# 1-Schematic_LED_Matrix.net
KiCad netlist of a schematic drawn in EasyEDA
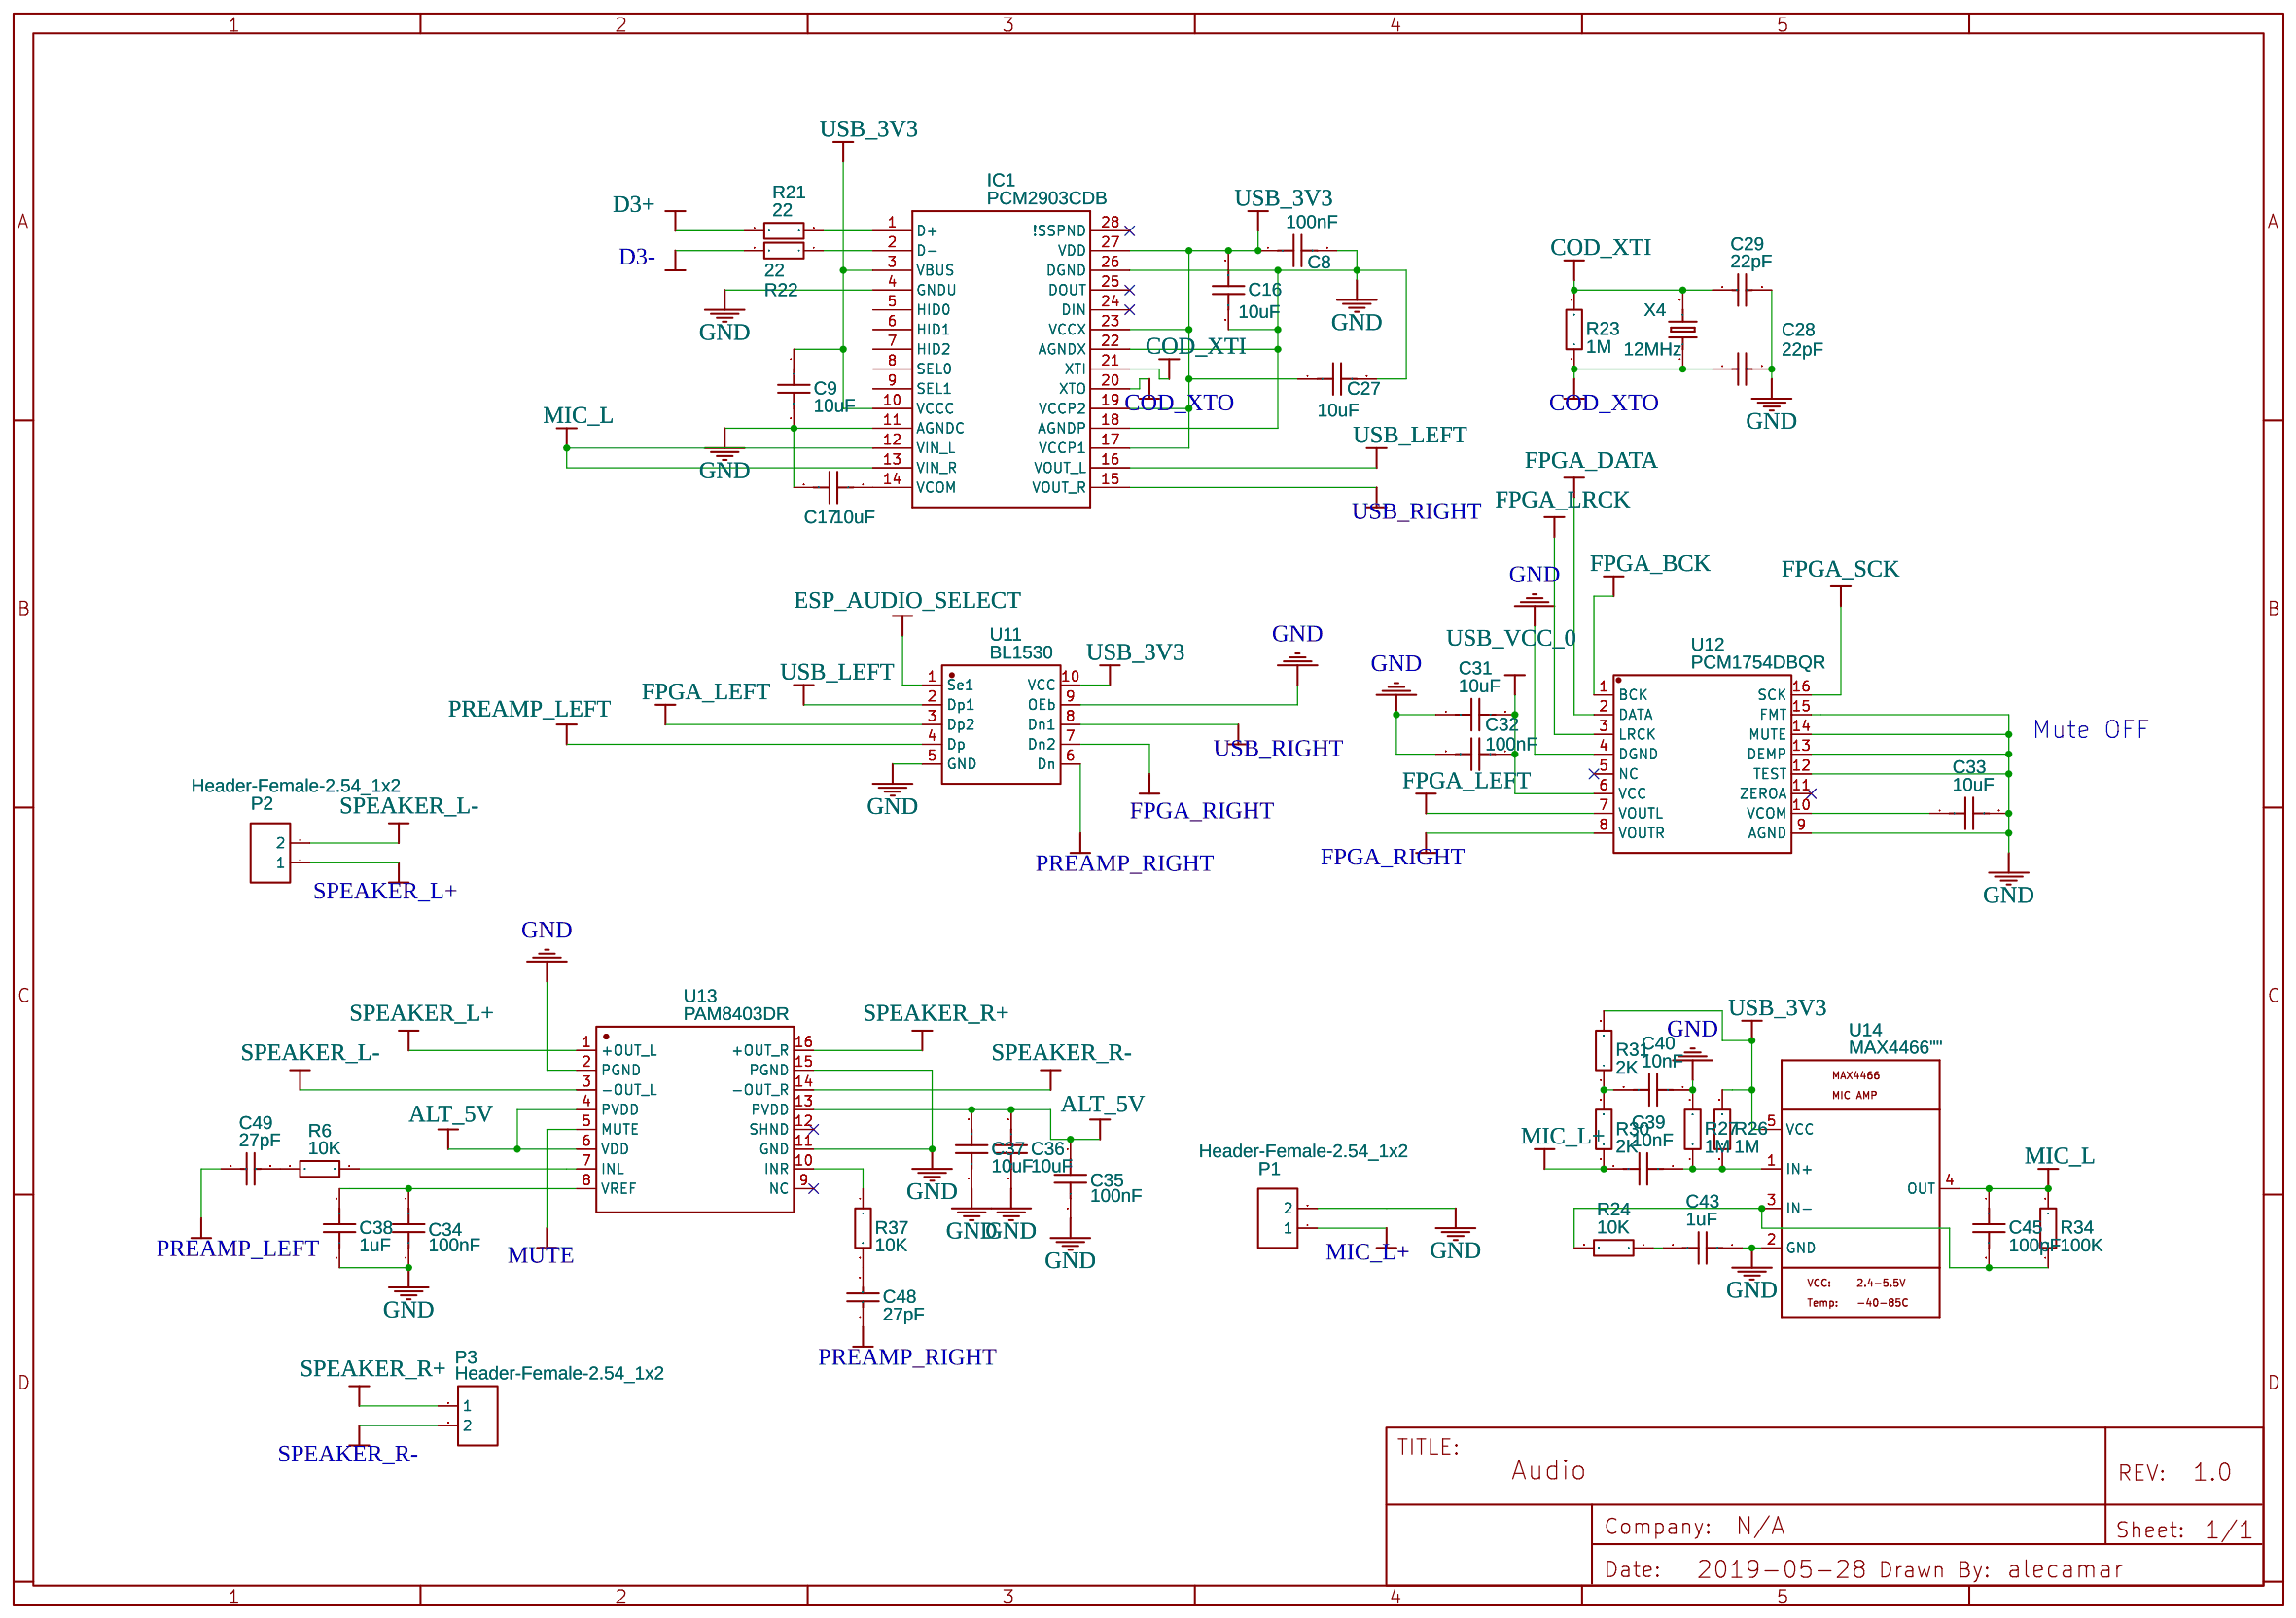
[diagram p0: Audio]
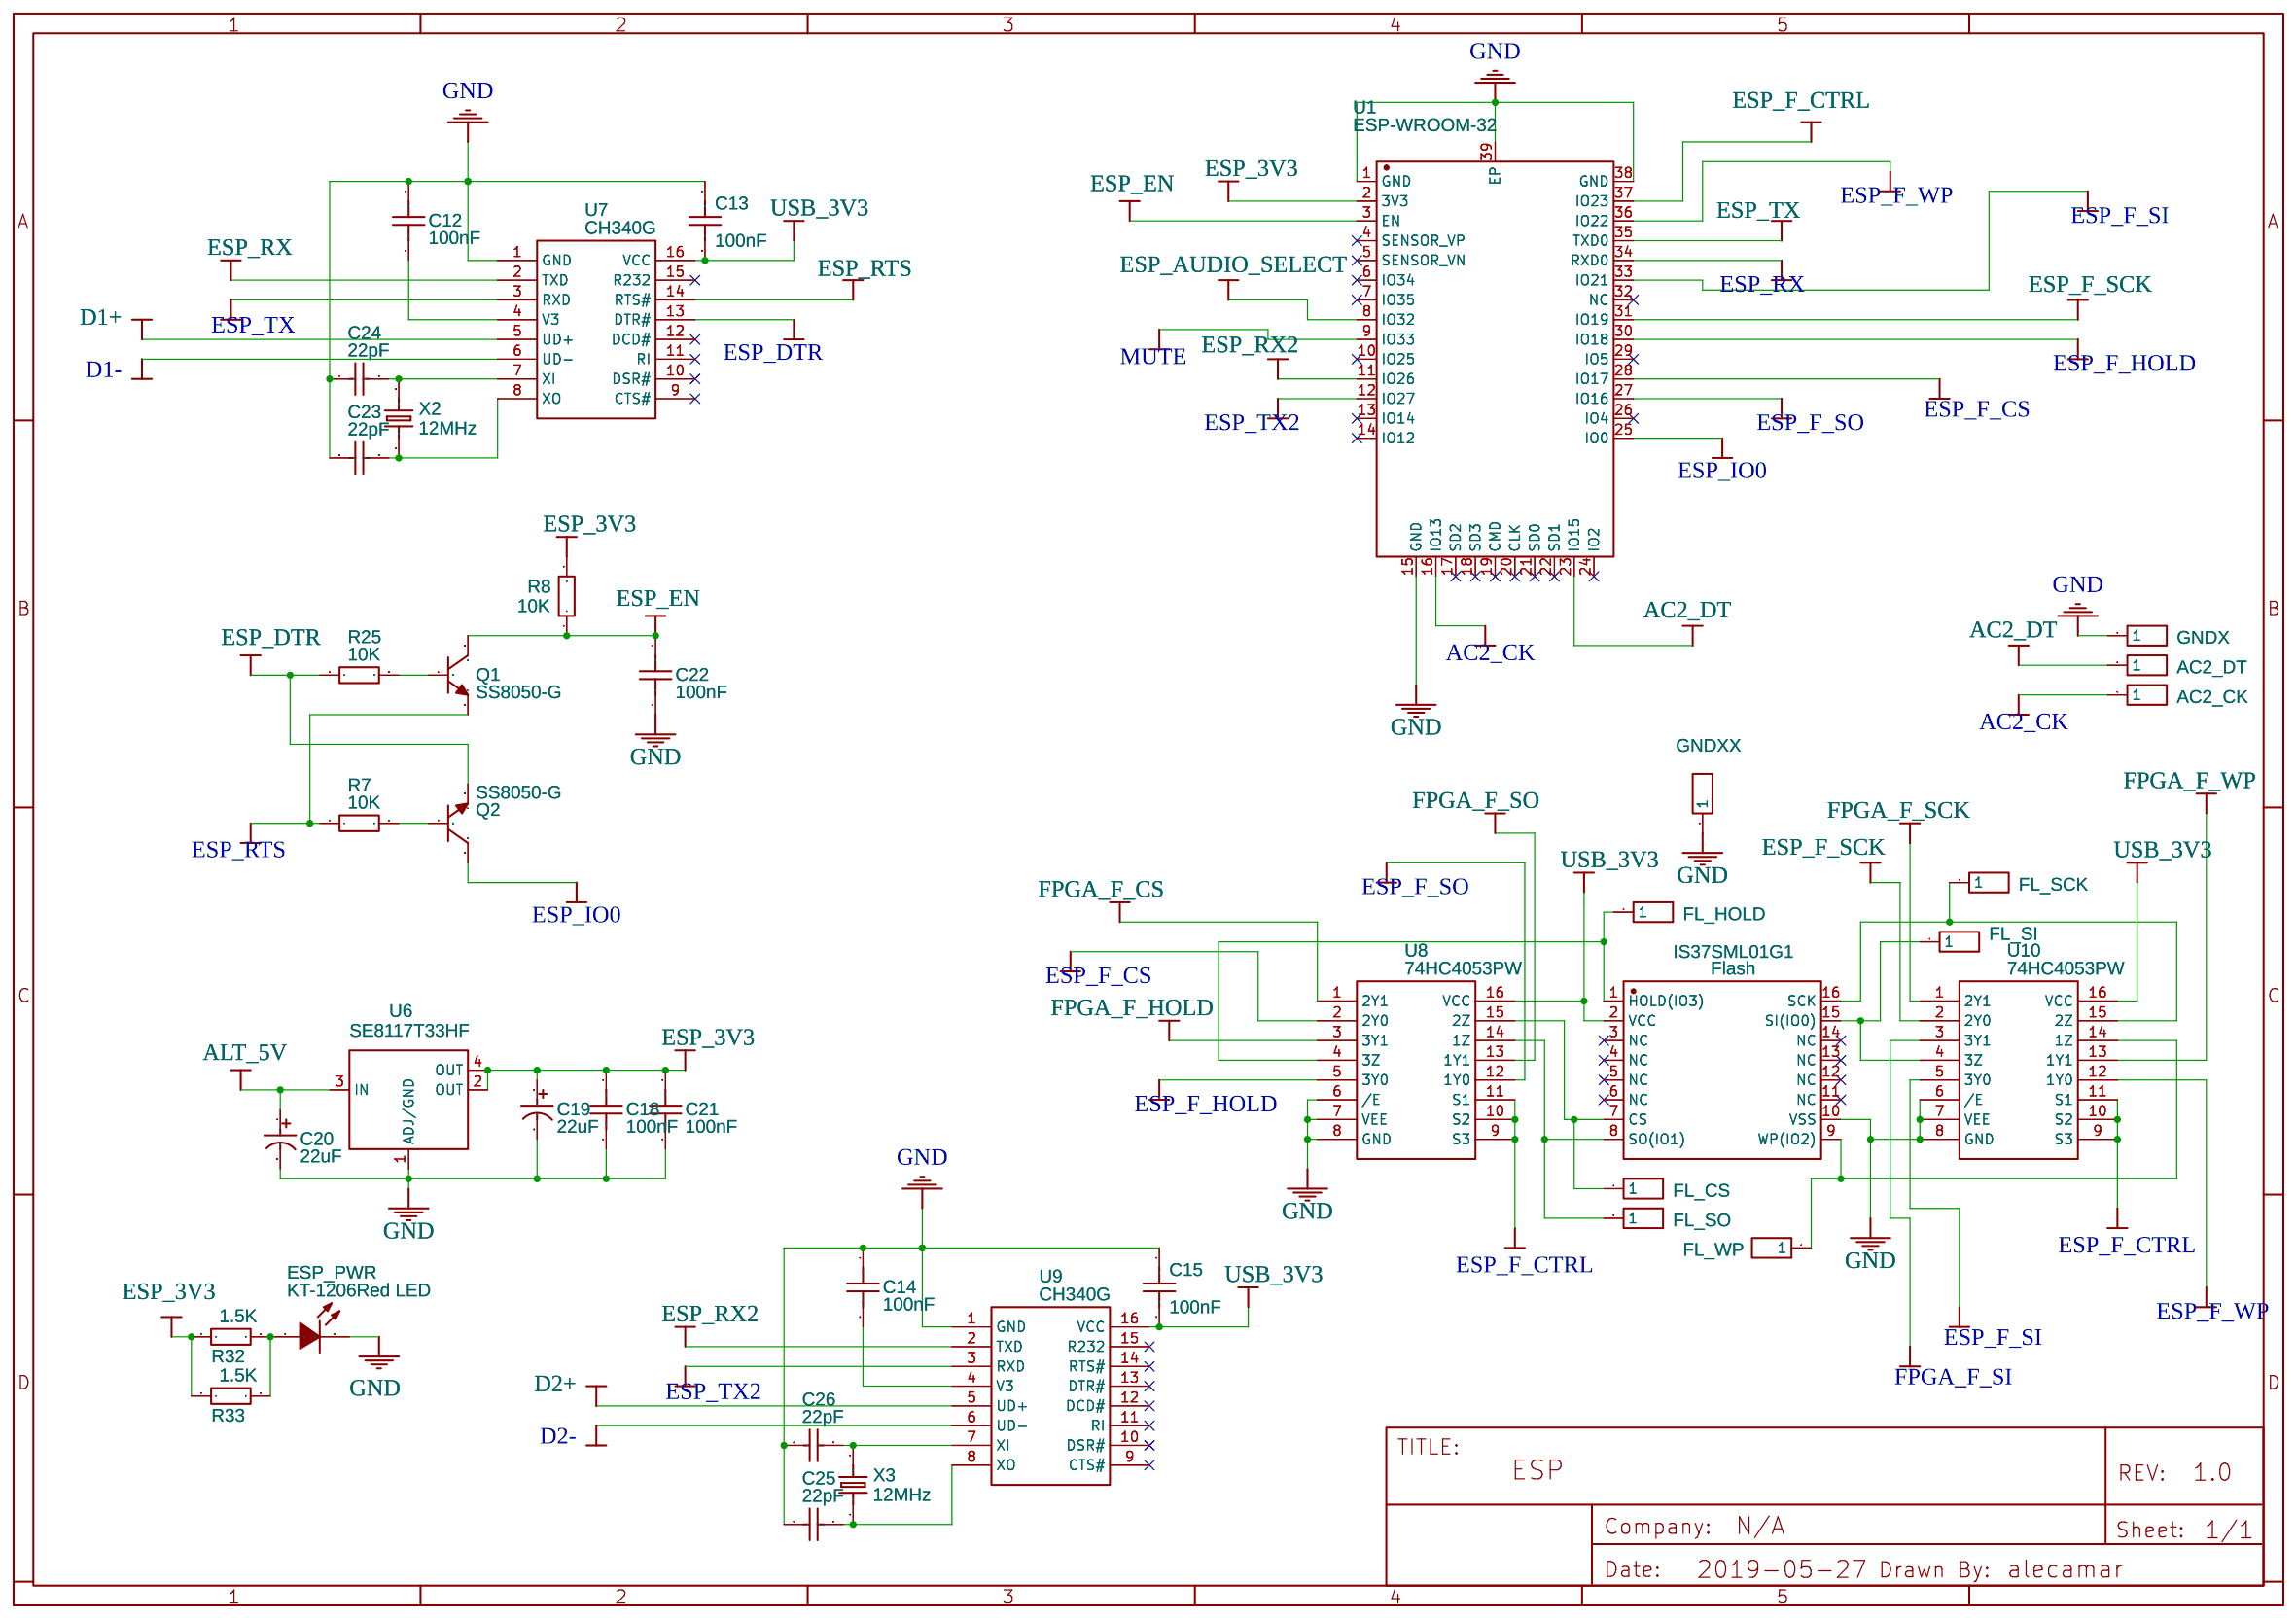
[diagram p1: ESP]
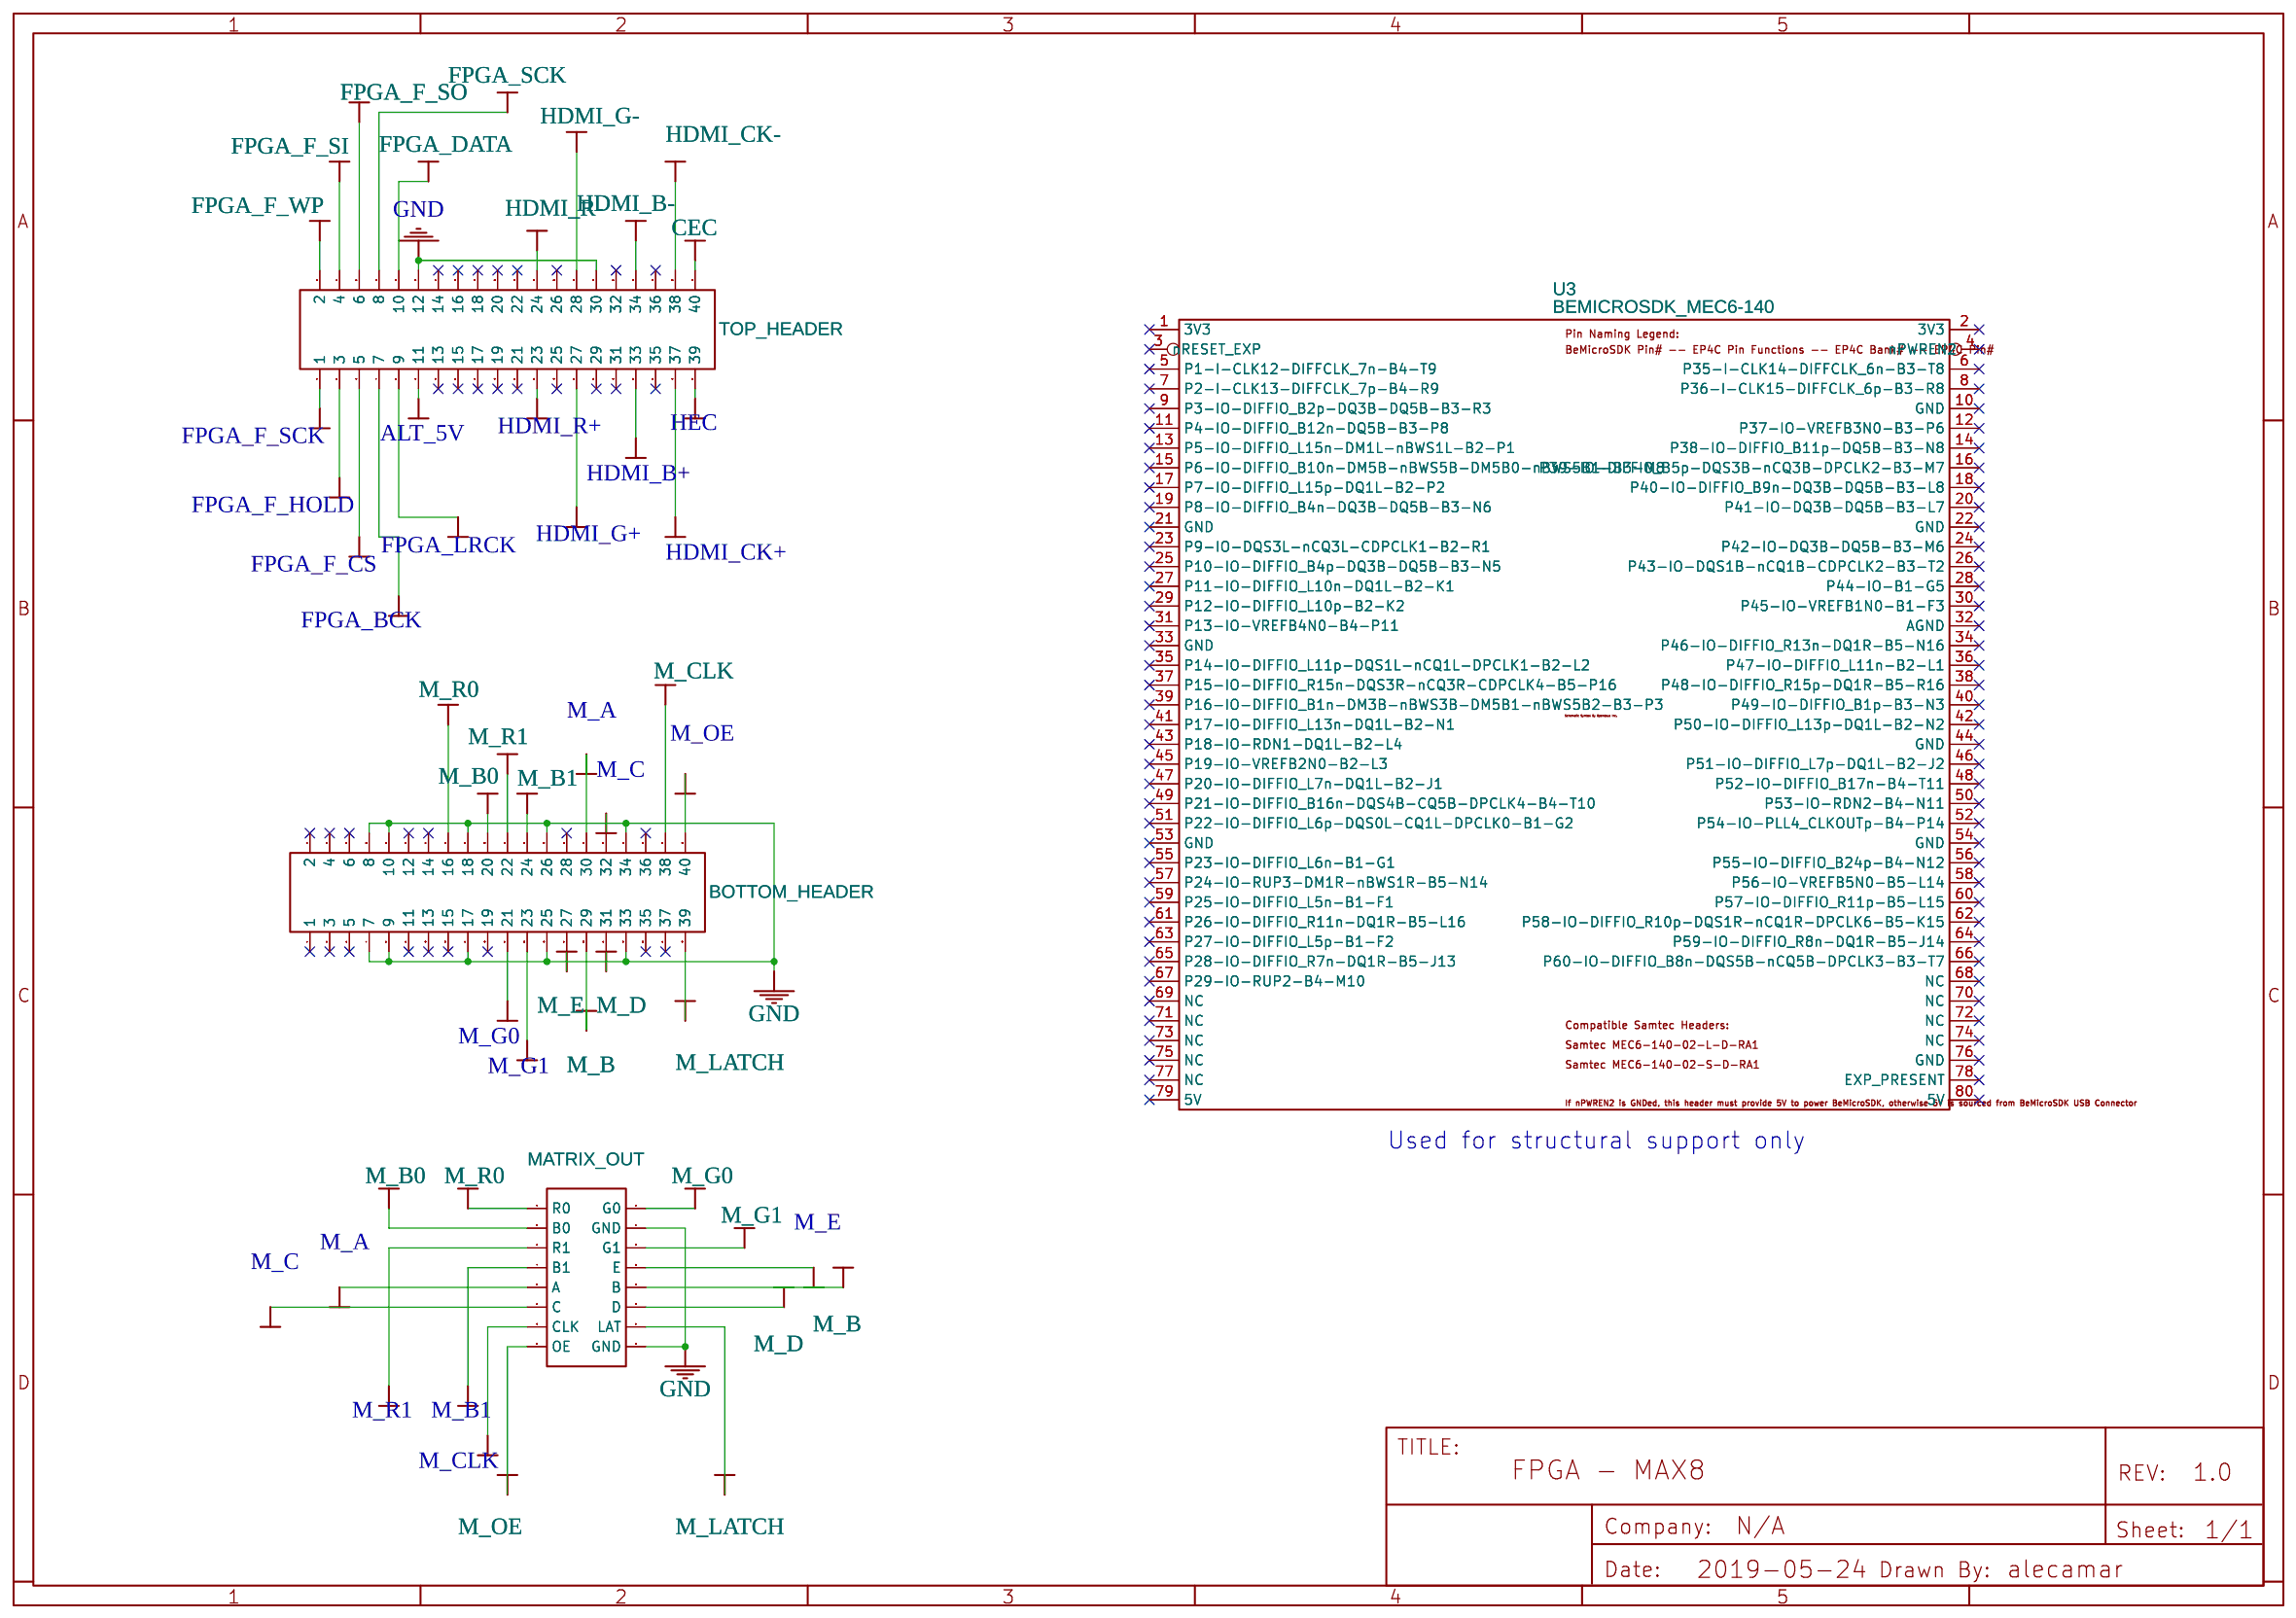
[diagram p2: FPGA]
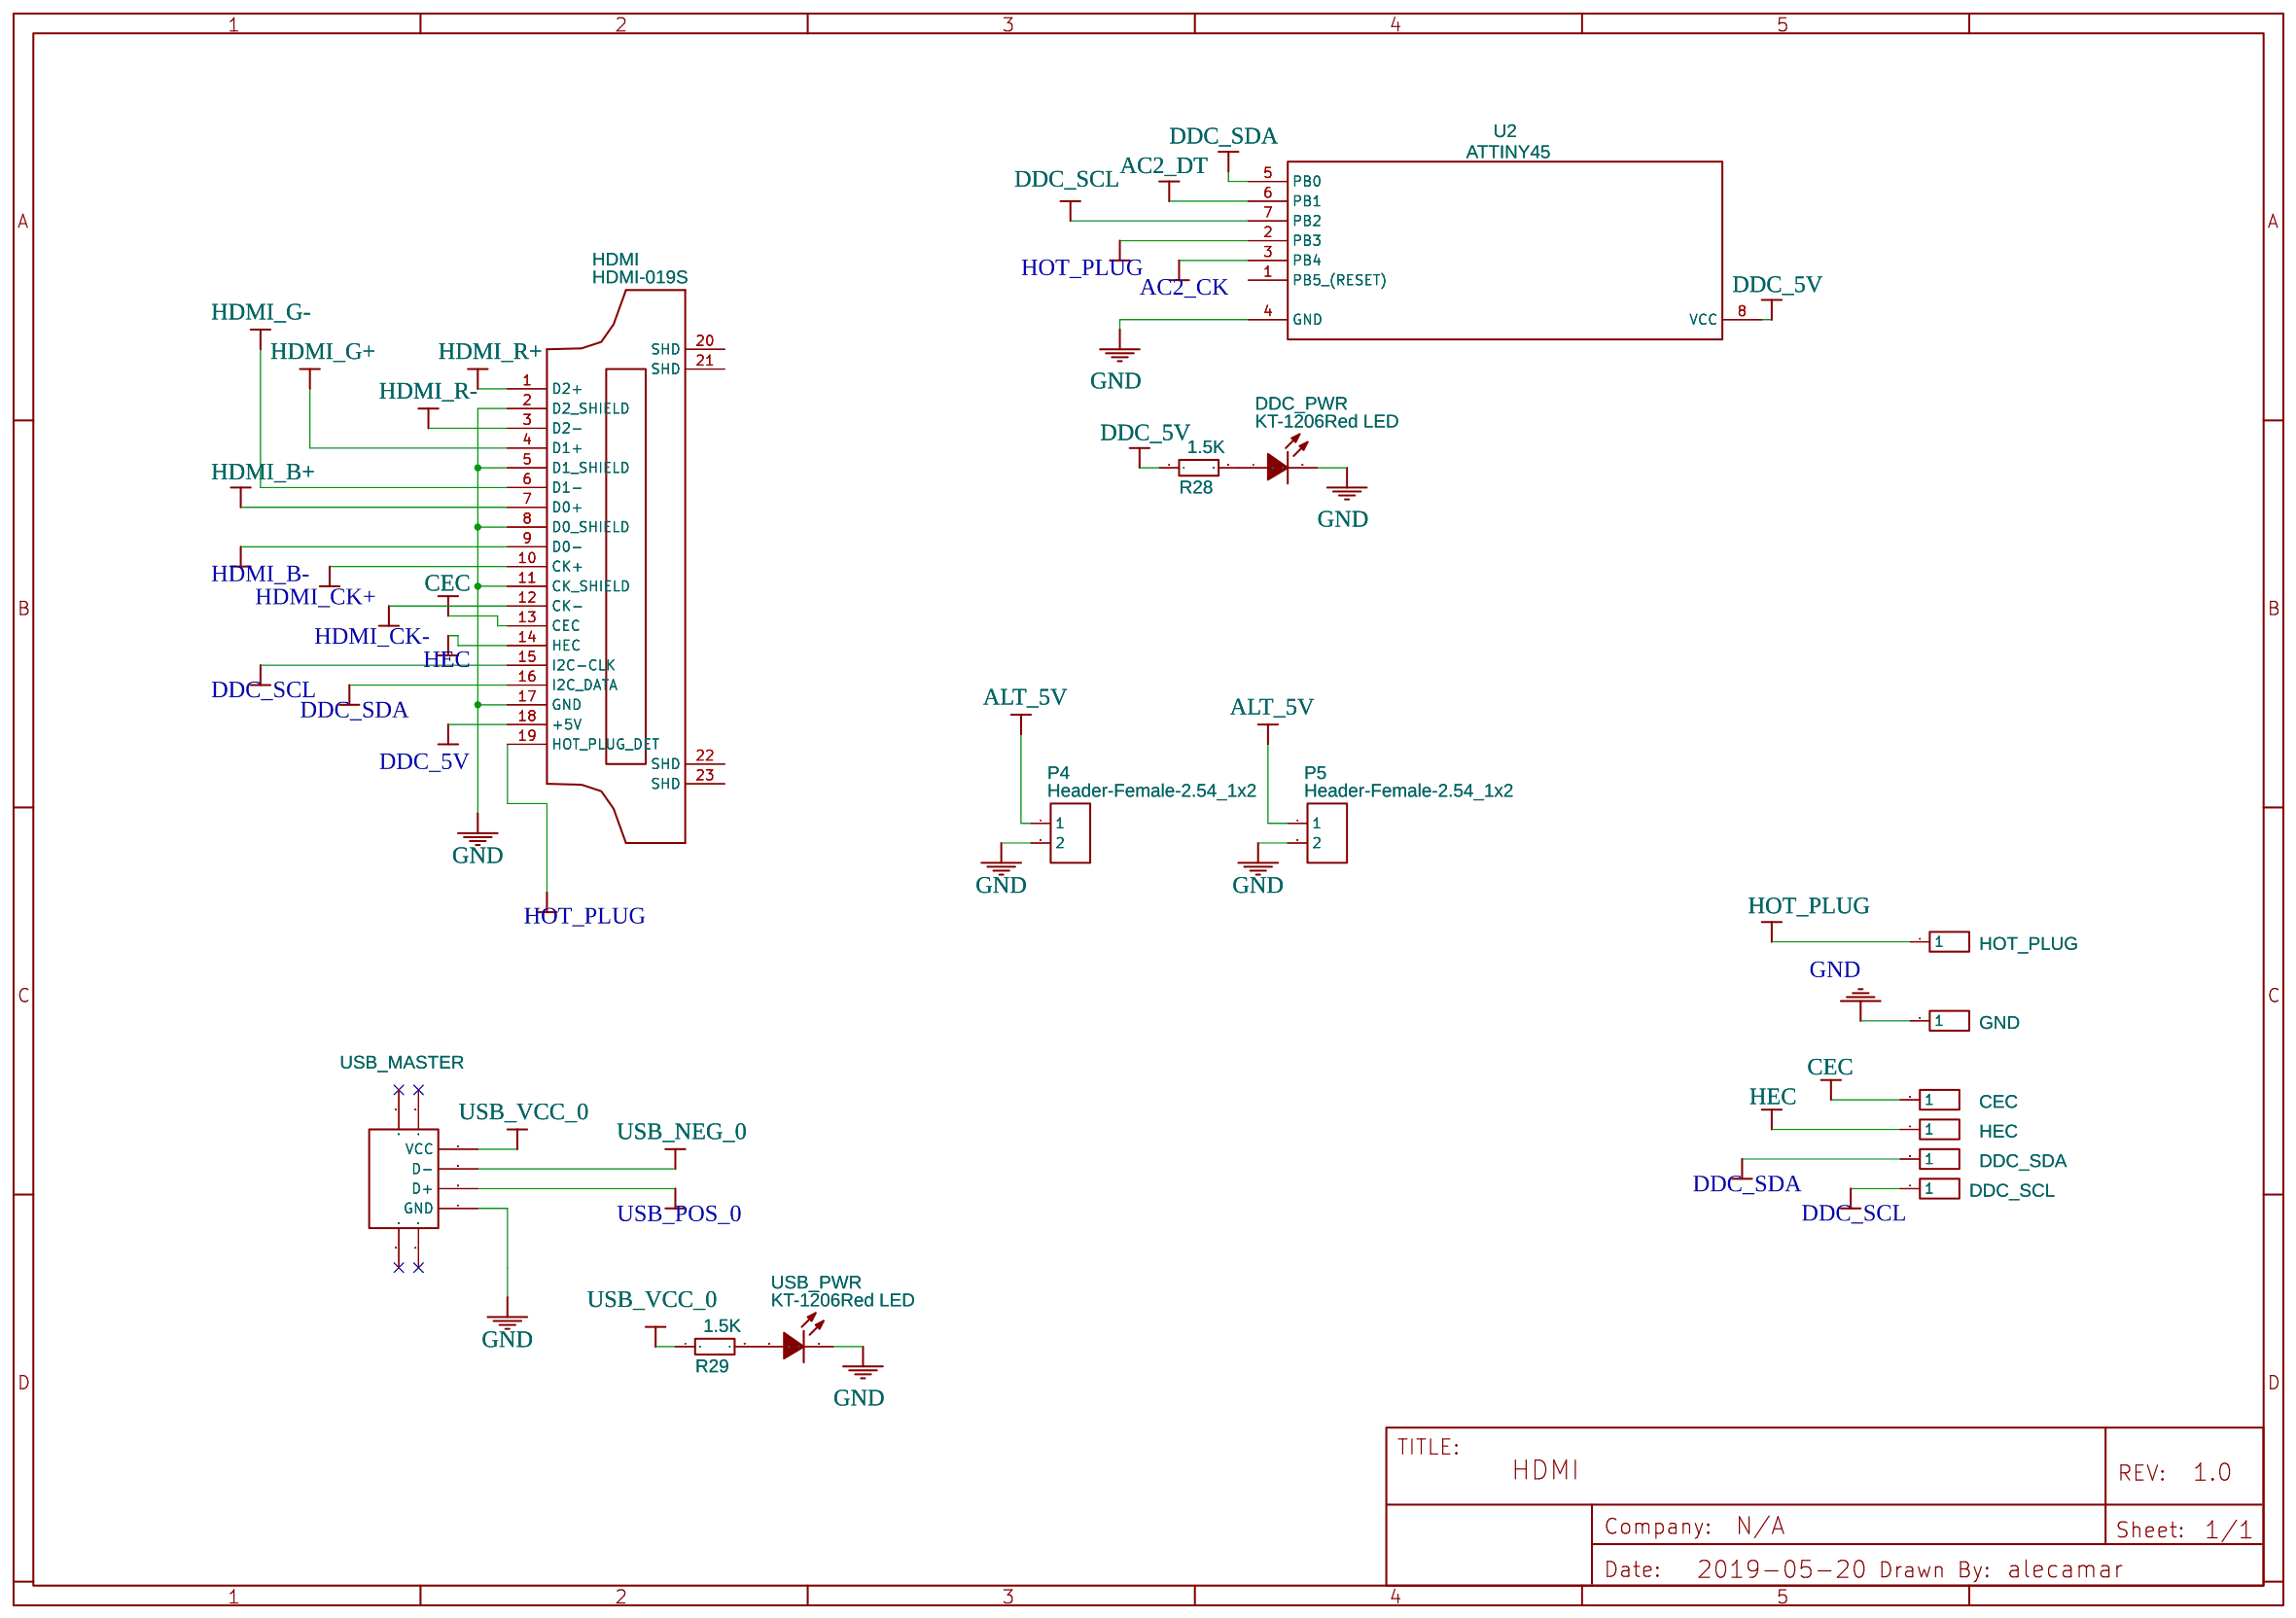
[diagram p3: IO]
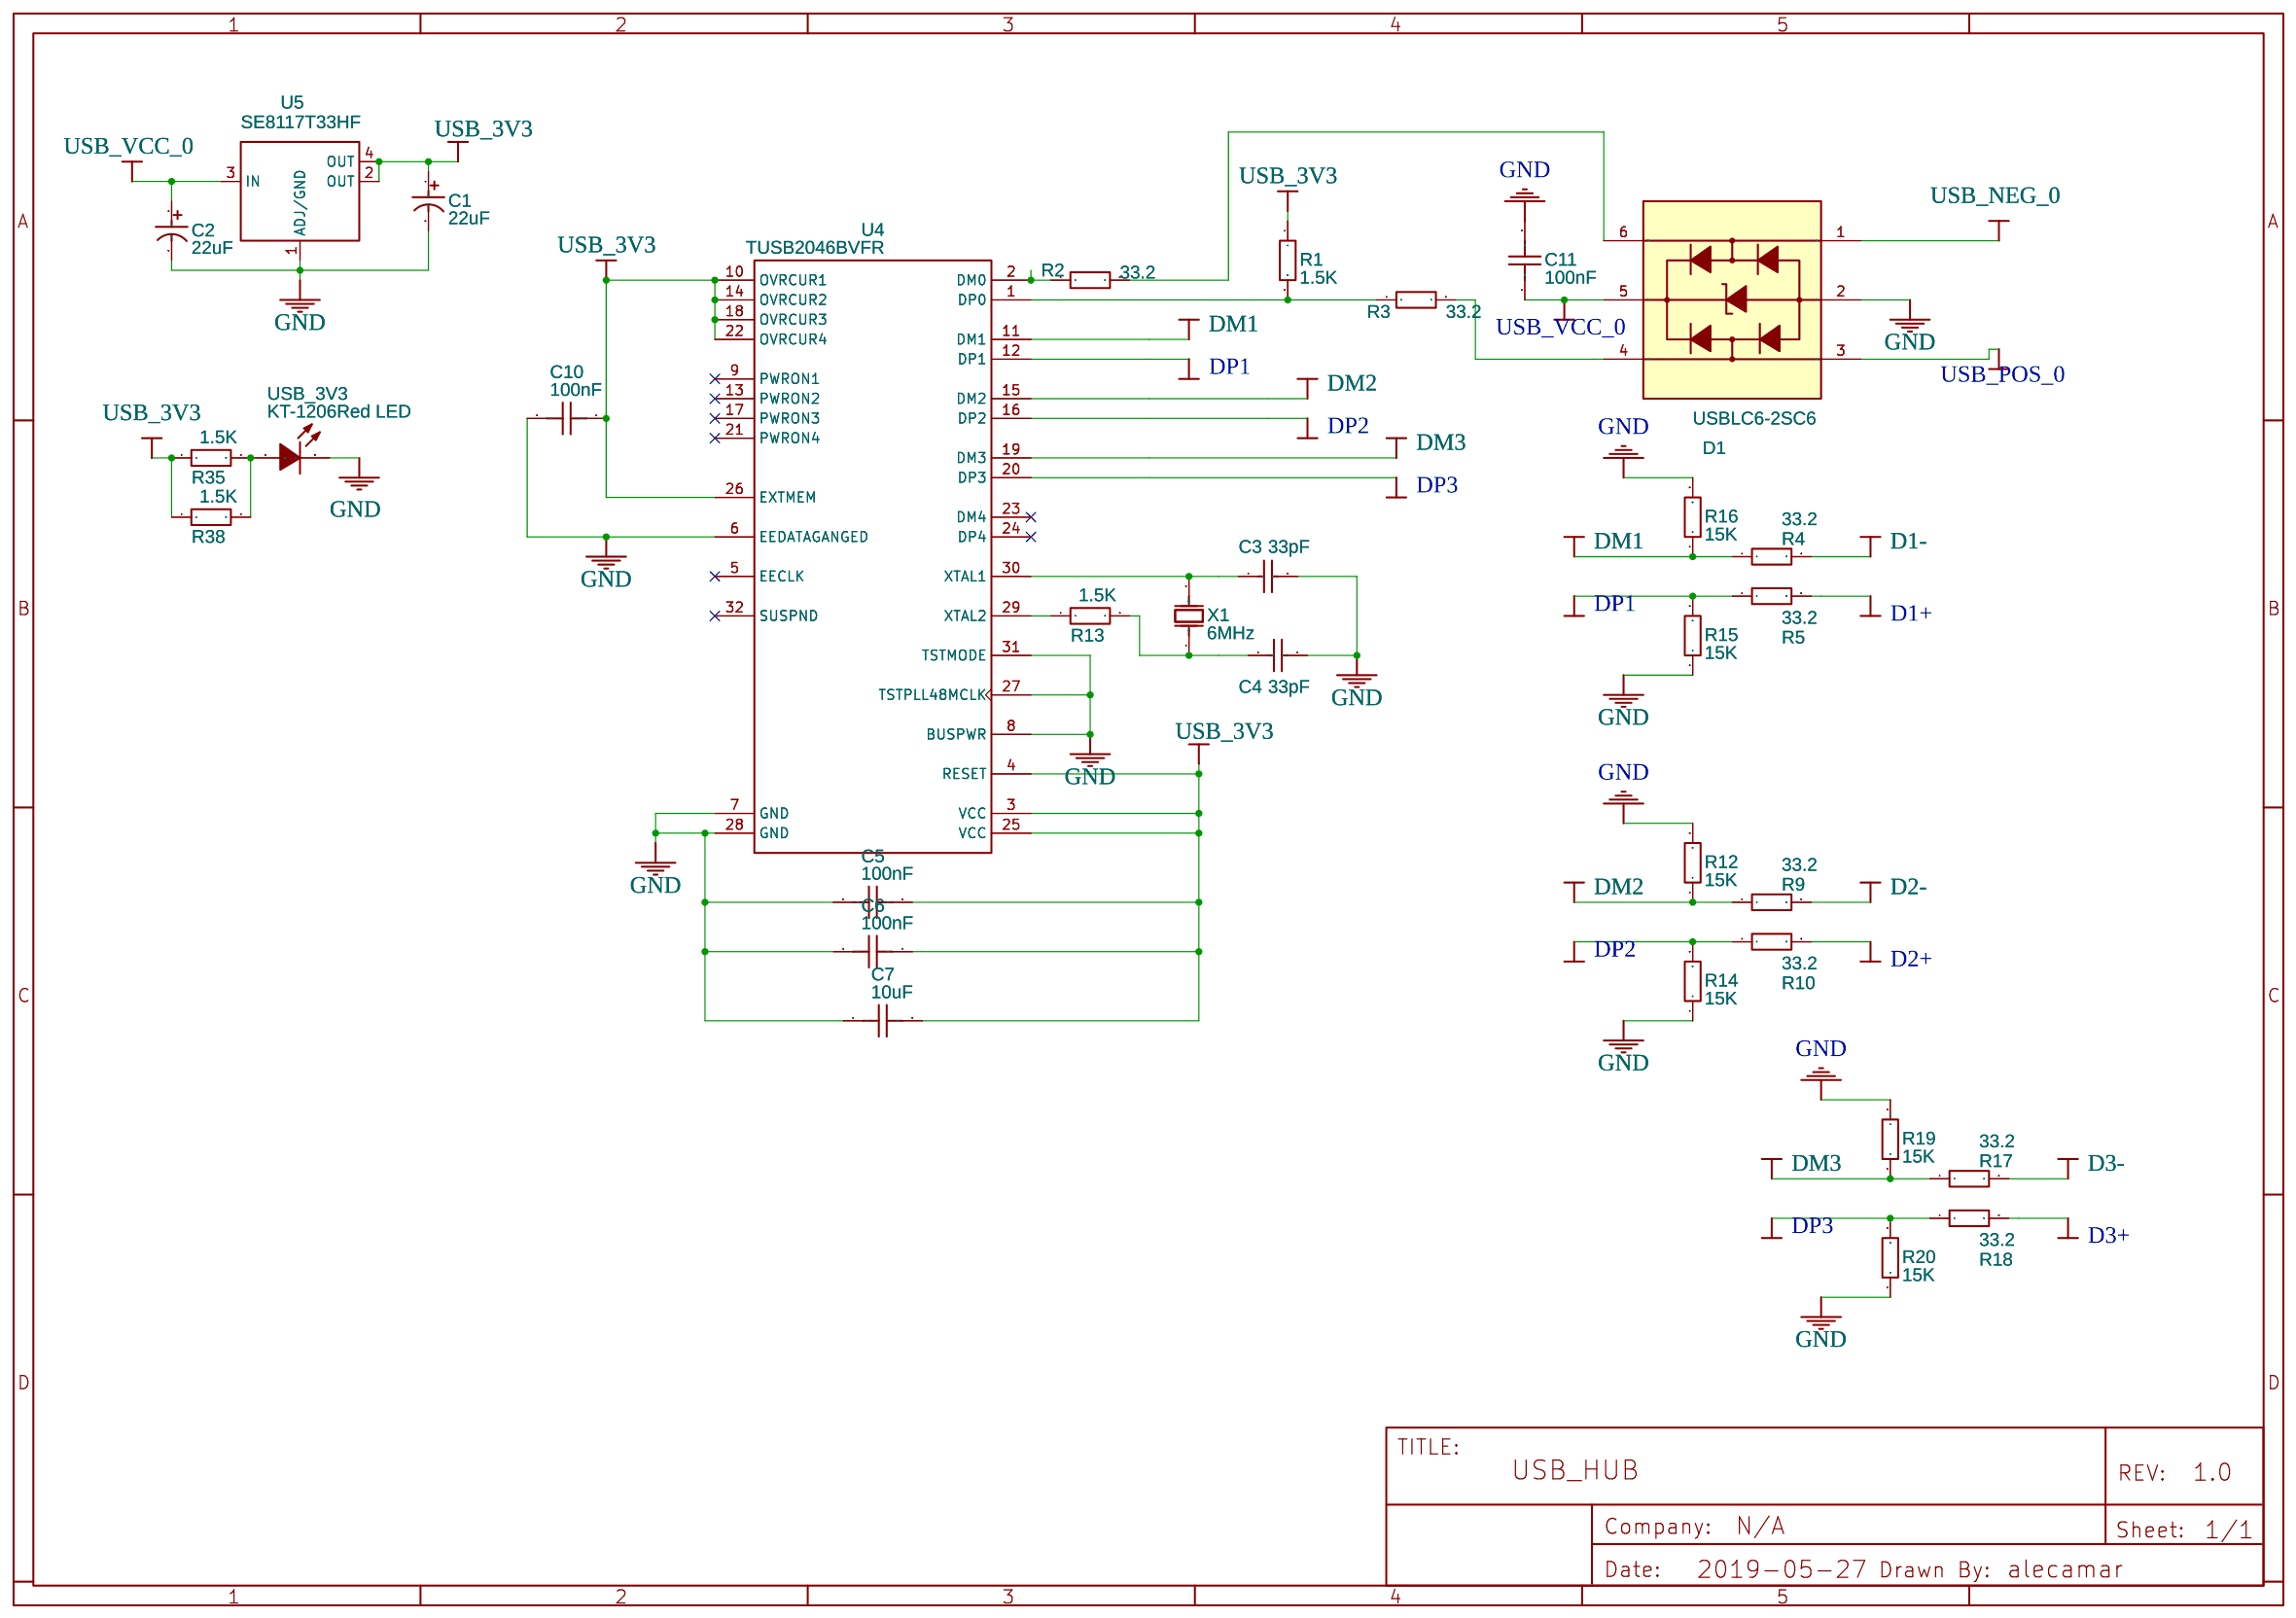
[diagram p4: USB_HUB]

(export (version "E")
  (design (tool "Eeschema 10.0.6"))
  (components
    (comp (ref "C8")
      (value "100nF")
      (fields
        (field (name "BOM_Manufacturer Part") "GRM319R71H104KA01D")
        (field (name "BOM_Supplier Part") "C86047")
      )
      (libsource (lib "") (part "GRM319R71H104KA01D_1"))
    )
    (comp (ref "C9")
      (value "10uF")
      (fields
        (field (name "BOM_Manufacturer Part") "GRM31MB31A106KE18L")
        (field (name "BOM_Supplier Part") "C162498")
      )
      (libsource (lib "") (part "GRM31MB31A106KE18L_2"))
    )
    (comp (ref "C16")
      (value "10uF")
      (fields
        (field (name "BOM_Manufacturer Part") "GRM31MB31A106KE18L")
        (field (name "BOM_Supplier Part") "C162498")
      )
      (libsource (lib "") (part "GRM31MB31A106KE18L_2"))
    )
    (comp (ref "C17")
      (value "10uF")
      (fields
        (field (name "BOM_Manufacturer Part") "GRM31MB31A106KE18L")
        (field (name "BOM_Supplier Part") "C162498")
      )
      (libsource (lib "") (part "GRM31MB31A106KE18L_3"))
    )
    (comp (ref "C27")
      (value "10uF")
      (fields
        (field (name "BOM_Manufacturer Part") "GRM31MB31A106KE18L")
        (field (name "BOM_Supplier Part") "C162498")
      )
      (libsource (lib "") (part "GRM31MB31A106KE18L"))
    )
    (comp (ref "C28")
      (value "22pF")
      (fields
        (field (name "BOM_Manufacturer Part") "1206CG220J500NT")
        (field (name "BOM_Supplier Part") "C1896")
      )
      (libsource (lib "") (part "1206CG220J500NT"))
    )
    (comp (ref "C29")
      (value "22pF")
      (fields
        (field (name "BOM_Manufacturer Part") "1206CG220J500NT")
        (field (name "BOM_Supplier Part") "C1896")
      )
      (libsource (lib "") (part "1206CG220J500NT"))
    )
    (comp (ref "C31")
      (value "10uF")
      (fields
        (field (name "BOM_Manufacturer Part") "GRM31MB31A106KE18L")
        (field (name "BOM_Supplier Part") "C162498")
      )
      (libsource (lib "") (part "GRM31MB31A106KE18L"))
    )
    (comp (ref "C32")
      (value "100nF")
      (fields
        (field (name "BOM_Manufacturer Part") "GRM319R71H104KA01D")
        (field (name "BOM_Supplier Part") "C86047")
      )
      (libsource (lib "") (part "GRM319R71H104KA01D_2"))
    )
    (comp (ref "C33")
      (value "10uF")
      (fields
        (field (name "BOM_Manufacturer Part") "GRM31MB31A106KE18L")
        (field (name "BOM_Supplier Part") "C162498")
      )
      (libsource (lib "") (part "GRM31MB31A106KE18L"))
    )
    (comp (ref "C34")
      (value "100nF")
      (fields
        (field (name "BOM_Manufacturer Part") "GRM319R71H104KA01D")
        (field (name "BOM_Supplier Part") "C86047")
      )
      (libsource (lib "") (part "GRM319R71H104KA01D"))
    )
    (comp (ref "C35")
      (value "100nF")
      (fields
        (field (name "BOM_Manufacturer Part") "GRM319R71H104KA01D")
        (field (name "BOM_Supplier Part") "C86047")
      )
      (libsource (lib "") (part "GRM319R71H104KA01D"))
    )
    (comp (ref "C36")
      (value "10uF")
      (fields
        (field (name "BOM_Manufacturer Part") "GRM31MB31A106KE18L")
        (field (name "BOM_Supplier Part") "C162498")
      )
      (libsource (lib "") (part "GRM31MB31A106KE18L_1"))
    )
    (comp (ref "C37")
      (value "10uF")
      (fields
        (field (name "BOM_Manufacturer Part") "GRM31MB31A106KE18L")
        (field (name "BOM_Supplier Part") "C162498")
      )
      (libsource (lib "") (part "GRM31MB31A106KE18L_1"))
    )
    (comp (ref "C38")
      (value "1uF")
      (fields
        (field (name "BOM_Manufacturer Part") "C1206C105M4RAC7800")
        (field (name "BOM_Supplier Part") "C141188")
      )
      (libsource (lib "") (part "C1206C105M4RAC7800_1"))
    )
    (comp (ref "C39")
      (value "10nF")
      (fields
        (field (name "BOM_Manufacturer Part") "TCC1206X7R103K102FT")
        (field (name "BOM_Supplier Part") "C344191")
      )
      (libsource (lib "") (part "TCC1206X7R103K102FT"))
    )
    (comp (ref "C40")
      (value "10nF")
      (fields
        (field (name "BOM_Manufacturer Part") "TCC1206X7R103K102FT")
        (field (name "BOM_Supplier Part") "C344191")
      )
      (libsource (lib "") (part "TCC1206X7R103K102FT"))
    )
    (comp (ref "C43")
      (value "1uF")
      (fields
        (field (name "BOM_Manufacturer Part") "C1206C105M4RAC7800")
        (field (name "BOM_Supplier Part") "C141188")
      )
      (libsource (lib "") (part "C1206C105M4RAC7800"))
    )
    (comp (ref "C45")
      (value "100pF")
      (fields
        (field (name "BOM_Manufacturer Part") "CL31C101JGFNNNE")
        (field (name "BOM_Supplier Part") "C159750")
      )
      (libsource (lib "") (part "CL31C101JGFNNNE"))
    )
    (comp (ref "C48")
      (value "27pF")
      (fields
        (field (name "BOM_Manufacturer Part") "1206CG270J500NT")
        (field (name "BOM_Supplier Part") "C1899")
      )
      (libsource (lib "") (part "1206CG270J500NT_1"))
    )
    (comp (ref "C49")
      (value "27pF")
      (fields
        (field (name "BOM_Manufacturer Part") "1206CG270J500NT")
        (field (name "BOM_Supplier Part") "C1899")
      )
      (libsource (lib "") (part "1206CG270J500NT"))
    )
    (comp (ref "IC1")
      (value "PCM2903CDB")
      (fields (field (name "BOM_Manufacturer Part") "?"))
      (libsource (lib "") (part "Unknown_455_110"))
    )
    (comp (ref "P1")
      (value "Header-Female-2.54_1x2")
      (fields
        (field (name "BOM_Manufacturer Part") "2.54-1*2PFemale")
        (field (name "BOM_Supplier Part") "C49661")
      )
      (libsource (lib "") (part "Unknown_645_610"))
    )
    (comp (ref "P2")
      (value "Header-Female-2.54_1x2")
      (fields
        (field (name "BOM_Manufacturer Part") "2.54-1*2PFemale")
        (field (name "BOM_Supplier Part") "C49661")
      )
      (libsource (lib "") (part "Unknown_135_425"))
    )
    (comp (ref "P3")
      (value "Header-Female-2.54_1x2")
      (fields
        (field (name "BOM_Manufacturer Part") "2.54-1*2PFemale")
        (field (name "BOM_Supplier Part") "C49661")
      )
      (libsource (lib "") (part "Unknown_230_710"))
    )
    (comp (ref "R6")
      (value "10K")
      (fields
        (field (name "BOM_Manufacturer Part") "TC0525D1002T5E")
        (field (name "BOM_Supplier Part") "C44791")
      )
      (libsource (lib "") (part "TC0525D1002T5E_1"))
    )
    (comp (ref "R21")
      (value "22")
      (fields
        (field (name "BOM_Manufacturer Part") "RMC1206225%N")
        (field (name "BOM_Supplier Part") "C325953")
      )
      (libsource (lib "") (part "RMC1206225%N_1"))
    )
    (comp (ref "R22")
      (value "22")
      (fields
        (field (name "BOM_Manufacturer Part") "RMC1206225%N")
        (field (name "BOM_Supplier Part") "C325953")
      )
      (libsource (lib "") (part "RMC1206225%N"))
    )
    (comp (ref "R23")
      (value "1M")
      (fields
        (field (name "BOM_Manufacturer Part") "RTT06105JTP")
        (field (name "BOM_Supplier Part") "C104604")
      )
      (libsource (lib "") (part "RTT06105JTP"))
    )
    (comp (ref "R24")
      (value "10K")
      (fields
        (field (name "BOM_Manufacturer Part") "TC0525D1002T5E")
        (field (name "BOM_Supplier Part") "C44791")
      )
      (libsource (lib "") (part "TC0525D1002T5E_1"))
    )
    (comp (ref "R26")
      (value "1M")
      (fields
        (field (name "BOM_Manufacturer Part") "RTT06105JTP")
        (field (name "BOM_Supplier Part") "C104604")
      )
      (libsource (lib "") (part "RTT06105JTP"))
    )
    (comp (ref "R27")
      (value "1M")
      (fields
        (field (name "BOM_Manufacturer Part") "RTT06105JTP")
        (field (name "BOM_Supplier Part") "C104604")
      )
      (libsource (lib "") (part "RTT06105JTP"))
    )
    (comp (ref "R30")
      (value "2K")
      (fields
        (field (name "BOM_Manufacturer Part") "AR06BTCV2001")
        (field (name "BOM_Supplier Part") "C319708")
      )
      (libsource (lib "") (part "AR06BTCV2001"))
    )
    (comp (ref "R31")
      (value "2K")
      (fields
        (field (name "BOM_Manufacturer Part") "AR06BTCV2001")
        (field (name "BOM_Supplier Part") "C319708")
      )
      (libsource (lib "") (part "AR06BTCV2001"))
    )
    (comp (ref "R34")
      (value "100K")
      (fields
        (field (name "BOM_Manufacturer Part") "AR06DTCV1003")
        (field (name "BOM_Supplier Part") "C319974")
      )
      (libsource (lib "") (part "AR06DTCV1003"))
    )
    (comp (ref "R37")
      (value "10K")
      (fields
        (field (name "BOM_Manufacturer Part") "TC0525D1002T5E")
        (field (name "BOM_Supplier Part") "C44791")
      )
      (libsource (lib "") (part "TC0525D1002T5E"))
    )
    (comp (ref "U11")
      (value "BL1530")
      (fields (field (name "BOM_Supplier Part") "C215758"))
      (libsource (lib "") (part "Unknown_500_360"))
    )
    (comp (ref "U12")
      (value "PCM1754DBQR")
      (fields (field (name "BOM_Supplier Part") "C294211"))
      (libsource (lib "") (part "Unknown_855_380"))
    )
    (comp (ref "U13")
      (value "PAM8403DR")
      (fields (field (name "BOM_Supplier Part") "C17337"))
      (libsource (lib "") (part "Unknown_345_560"))
    )
    (comp (ref "U14")
      (value "MAX4466\"\"")
      (fields (field (name "BOM_Manufacturer Part") "?"))
      (libsource (lib "") (part "Unknown_895_585"))
    )
    (comp (ref "X4")
      (value "12MHz")
      (fields
        (field (name "BOM_Manufacturer Part") "HC-49S12MHz20pF30PPM")
        (field (name "BOM_Supplier Part") "C127674")
      )
      (libsource (lib "") (part "HC-49S12MHZ20PF30PPM"))
    )
    (comp (ref "AC2_CK")
      (value "TestPoint")
      (fields
        (field (name "BOM_Manufacturer Part") "Header-Male-2.54_1x1")
        (field (name "BOM_Supplier Part") "C81276")
      )
      (libsource (lib "") (part "Unknown_1075_345"))
    )
    (comp (ref "AC2_DT")
      (value "TestPoint")
      (fields
        (field (name "BOM_Manufacturer Part") "Header-Male-2.54_1x1")
        (field (name "BOM_Supplier Part") "C81276")
      )
      (libsource (lib "") (part "Unknown_1075_330"))
    )
    (comp (ref "C12")
      (value "100nF")
      (fields
        (field (name "BOM_Manufacturer Part") "GRM319R71H104KA01D")
        (field (name "BOM_Supplier Part") "C86047")
      )
      (libsource (lib "") (part "GRM319R71H104KA01D"))
    )
    (comp (ref "C13")
      (value "100nF")
      (fields
        (field (name "BOM_Manufacturer Part") "GRM319R71H104KA01D")
        (field (name "BOM_Supplier Part") "C86047")
      )
      (libsource (lib "") (part "GRM319R71H104KA01D"))
    )
    (comp (ref "C14")
      (value "100nF")
      (fields
        (field (name "BOM_Manufacturer Part") "GRM319R71H104KA01D")
        (field (name "BOM_Supplier Part") "C86047")
      )
      (libsource (lib "") (part "GRM319R71H104KA01D"))
    )
    (comp (ref "C15")
      (value "100nF")
      (fields
        (field (name "BOM_Manufacturer Part") "GRM319R71H104KA01D")
        (field (name "BOM_Supplier Part") "C86047")
      )
      (libsource (lib "") (part "GRM319R71H104KA01D"))
    )
    (comp (ref "C18")
      (value "100nF")
      (fields
        (field (name "BOM_Manufacturer Part") "GRM319R71H104KA01D")
        (field (name "BOM_Supplier Part") "C86047")
      )
      (libsource (lib "") (part "GRM319R71H104KA01D"))
    )
    (comp (ref "C19")
      (value "22uF")
      (fields
        (field (name "BOM_Manufacturer Part") "22uF 16V 4*5")
        (field (name "BOM_Supplier Part") "C43800")
      )
      (libsource (lib "") (part "22uF 16V 4*5"))
    )
    (comp (ref "C20")
      (value "22uF")
      (fields
        (field (name "BOM_Manufacturer Part") "22uF 16V 4*5")
        (field (name "BOM_Supplier Part") "C43800")
      )
      (libsource (lib "") (part "22uF 16V 4*5"))
    )
    (comp (ref "C21")
      (value "100nF")
      (fields
        (field (name "BOM_Manufacturer Part") "GRM319R71H104KA01D")
        (field (name "BOM_Supplier Part") "C86047")
      )
      (libsource (lib "") (part "GRM319R71H104KA01D"))
    )
    (comp (ref "C22")
      (value "100nF")
      (fields
        (field (name "BOM_Manufacturer Part") "GRM319R71H104KA01D")
        (field (name "BOM_Supplier Part") "C86047")
      )
      (libsource (lib "") (part "GRM319R71H104KA01D"))
    )
    (comp (ref "C23")
      (value "22pF")
      (fields
        (field (name "BOM_Manufacturer Part") "1206CG220J500NT")
        (field (name "BOM_Supplier Part") "C1896")
      )
      (libsource (lib "") (part "1206CG220J500NT"))
    )
    (comp (ref "C24")
      (value "22pF")
      (fields
        (field (name "BOM_Manufacturer Part") "1206CG220J500NT")
        (field (name "BOM_Supplier Part") "C1896")
      )
      (libsource (lib "") (part "1206CG220J500NT"))
    )
    (comp (ref "C25")
      (value "22pF")
      (fields
        (field (name "BOM_Manufacturer Part") "1206CG220J500NT")
        (field (name "BOM_Supplier Part") "C1896")
      )
      (libsource (lib "") (part "1206CG220J500NT"))
    )
    (comp (ref "C26")
      (value "22pF")
      (fields
        (field (name "BOM_Manufacturer Part") "1206CG220J500NT")
        (field (name "BOM_Supplier Part") "C1896")
      )
      (libsource (lib "") (part "1206CG220J500NT"))
    )
    (comp (ref "ESP_PWR")
      (value "KT-1206Red LED")
      (fields (field (name "BOM_Supplier Part") "C49018"))
      (libsource (lib "") (part "Unknown_150_665"))
    )
    (comp (ref "FL_CS")
      (value "TestPoint")
      (fields
        (field (name "BOM_Manufacturer Part") "Header-Male-2.54_1x1")
        (field (name "BOM_Supplier Part") "C81276")
      )
      (libsource (lib "") (part "Unknown_820_595"))
    )
    (comp (ref "FL_HOLD")
      (value "TestPoint")
      (fields
        (field (name "BOM_Manufacturer Part") "Header-Male-2.54_1x1")
        (field (name "BOM_Supplier Part") "C81276")
      )
      (libsource (lib "") (part "Unknown_825_455"))
    )
    (comp (ref "FL_SCK")
      (value "TestPoint")
      (fields
        (field (name "BOM_Manufacturer Part") "Header-Male-2.54_1x1")
        (field (name "BOM_Supplier Part") "C81276")
      )
      (libsource (lib "") (part "Unknown_995_440"))
    )
    (comp (ref "FL_SI")
      (value "TestPoint")
      (fields
        (field (name "BOM_Manufacturer Part") "Header-Male-2.54_1x1")
        (field (name "BOM_Supplier Part") "C81276")
      )
      (libsource (lib "") (part "Unknown_980_470"))
    )
    (comp (ref "FL_SO")
      (value "TestPoint")
      (fields
        (field (name "BOM_Manufacturer Part") "Header-Male-2.54_1x1")
        (field (name "BOM_Supplier Part") "C81276")
      )
      (libsource (lib "") (part "Unknown_820_610"))
    )
    (comp (ref "FL_WP")
      (value "TestPoint")
      (fields
        (field (name "BOM_Manufacturer Part") "Header-Male-2.54_1x1")
        (field (name "BOM_Supplier Part") "C81276")
      )
      (libsource (lib "") (part "Unknown_895_625"))
    )
    (comp (ref "GNDX")
      (value "TestPoint")
      (fields
        (field (name "BOM_Manufacturer Part") "Header-Male-2.54_1x1")
        (field (name "BOM_Supplier Part") "C81276")
      )
      (libsource (lib "") (part "Unknown_1075_315"))
    )
    (comp (ref "GNDXX")
      (value "TestPoint")
      (fields
        (field (name "BOM_Manufacturer Part") "Header-Male-2.54_1x1")
        (field (name "BOM_Supplier Part") "C81276")
      )
      (libsource (lib "") (part "Unknown_855_400"))
    )
    (comp (ref "IS37SML01G1") (value "Flash") (libsource (lib "") (part "Unknown_865_535")))
    (comp (ref "Q1")
      (value "SS8050-G")
      (fields (field (name "BOM_Supplier Part") "C164886"))
      (libsource (lib "") (part "Unknown_220_335"))
    )
    (comp (ref "Q2")
      (value "SS8050-G")
      (fields (field (name "BOM_Supplier Part") "C164886"))
      (libsource (lib "") (part "Unknown_220_410"))
    )
    (comp (ref "R7")
      (value "10K")
      (fields
        (field (name "BOM_Manufacturer Part") "CR1210J30103G")
        (field (name "BOM_Supplier Part") "C102401")
      )
      (libsource (lib "") (part "CR1210J30103G"))
    )
    (comp (ref "R8")
      (value "10K")
      (fields
        (field (name "BOM_Manufacturer Part") "CR1210J30103G")
        (field (name "BOM_Supplier Part") "C102401")
      )
      (libsource (lib "") (part "CR1210J30103G_1"))
    )
    (comp (ref "R25")
      (value "10K")
      (fields
        (field (name "BOM_Manufacturer Part") "CR1210J30103G")
        (field (name "BOM_Supplier Part") "C102401")
      )
      (libsource (lib "") (part "CR1210J30103G"))
    )
    (comp (ref "R32")
      (value "1.5K")
      (fields
        (field (name "BOM_Manufacturer Part") "AC1206JR-071K5L")
        (field (name "BOM_Supplier Part") "C144466")
      )
      (libsource (lib "") (part "AC1206JR-071K5L"))
    )
    (comp (ref "R33")
      (value "1.5K")
      (fields
        (field (name "BOM_Manufacturer Part") "AC1206JR-071K5L")
        (field (name "BOM_Supplier Part") "C144466")
      )
      (libsource (lib "") (part "AC1206JR-071K5L"))
    )
    (comp (ref "U1")
      (value "ESP-WROOM-32")
      (fields (field (name "BOM_Supplier Part") "C95209"))
      (libsource (lib "") (part "Unknown_750_180"))
    )
    (comp (ref "U6")
      (value "SE8117T33HF")
      (fields (field (name "BOM_Supplier Part") "C115002"))
      (libsource (lib "") (part "Unknown_200_560"))
    )
    (comp (ref "U7")
      (value "CH340G")
      (fields (field (name "BOM_Supplier Part") "C14267"))
      (libsource (lib "") (part "Unknown_295_165"))
    )
    (comp (ref "U8")
      (value "74HC4053PW")
      (fields (field (name "BOM_Supplier Part") "C5648"))
      (libsource (lib "") (part "Unknown_710_535"))
    )
    (comp (ref "U9")
      (value "CH340G")
      (fields (field (name "BOM_Supplier Part") "C14267"))
      (libsource (lib "") (part "Unknown_525_705"))
    )
    (comp (ref "U10")
      (value "74HC4053PW")
      (fields (field (name "BOM_Supplier Part") "C5648"))
      (libsource (lib "") (part "Unknown_1015_535"))
    )
    (comp (ref "X2")
      (value "12MHz")
      (fields
        (field (name "BOM_Manufacturer Part") "HC-49S12MHz20pF30PPM")
        (field (name "BOM_Supplier Part") "C127674")
      )
      (libsource (lib "") (part "HC-49S12MHZ20PF30PPM"))
    )
    (comp (ref "X3")
      (value "12MHz")
      (fields
        (field (name "BOM_Manufacturer Part") "HC-49S12MHz20pF30PPM")
        (field (name "BOM_Supplier Part") "C127674")
      )
      (libsource (lib "") (part "HC-49S12MHZ20PF30PPM"))
    )
    (comp (ref "BOTTOM_HEADER")
      (value "Header-Male-2.54_2x20")
      (fields (field (name "BOM_Supplier Part") "C50980"))
      (libsource (lib "") (part "Unknown_245_445"))
    )
    (comp (ref "MATRIX_OUT")
      (value "MATRIX_OUT")
      (fields
        (field (name "BOM_Manufacturer Part") "Double row straight 2*8Headers  Pins 2.54mm")
        (field (name "BOM_Supplier Part") "C68234")
      )
      (libsource (lib "") (part "Unknown_290_640"))
    )
    (comp (ref "TOP_HEADER")
      (value "Header-Mal0")
      (fields
        (field (name "BOM_Manufacturer Part") "Header-Male-2.54_2x20")
        (field (name "BOM_Supplier Part") "C50980")
      )
      (libsource (lib "") (part "Unknown_250_160"))
    )
    (comp (ref "U3")
      (value "BEMICROSDK_MEC6-140")
      (fields (field (name "BOM_Manufacturer Part") "?"))
      (libsource (lib "") (part "Unknown_785_355"))
    )
    (comp (ref "CEC")
      (value "TestPoint")
      (fields
        (field (name "BOM_Manufacturer Part") "Header-Male-2.54_1x1")
        (field (name "BOM_Supplier Part") "C81276")
      )
      (libsource (lib "") (part "Unknown_970_550"))
    )
    (comp (ref "DDC_PWR")
      (value "KT-1206Red LED")
      (fields (field (name "BOM_Supplier Part") "C49018"))
      (libsource (lib "") (part "Unknown_640_225"))
    )
    (comp (ref "DDC_SCL")
      (value "TestPoint")
      (fields
        (field (name "BOM_Manufacturer Part") "Header-Male-2.54_1x1")
        (field (name "BOM_Supplier Part") "C81276")
      )
      (libsource (lib "") (part "Unknown_970_595"))
    )
    (comp (ref "DDC_SDA")
      (value "TestPoint")
      (fields
        (field (name "BOM_Manufacturer Part") "Header-Male-2.54_1x1")
        (field (name "BOM_Supplier Part") "C81276")
      )
      (libsource (lib "") (part "Unknown_970_580"))
    )
    (comp (ref "GND")
      (value "TestPoint")
      (fields
        (field (name "BOM_Manufacturer Part") "Header-Male-2.54_1x1")
        (field (name "BOM_Supplier Part") "C81276")
      )
      (libsource (lib "") (part "Unknown_975_510"))
    )
    (comp (ref "HDMI")
      (value "HDMI-019S")
      (fields (field (name "BOM_Supplier Part") "C111617"))
      (libsource (lib "") (part "Unknown_305_280"))
    )
    (comp (ref "HEC")
      (value "TestPoint")
      (fields
        (field (name "BOM_Manufacturer Part") "Header-Male-2.54_1x1")
        (field (name "BOM_Supplier Part") "C81276")
      )
      (libsource (lib "") (part "Unknown_970_565"))
    )
    (comp (ref "HOT_PLUG")
      (value "TestPoint")
      (fields
        (field (name "BOM_Manufacturer Part") "Header-Male-2.54_1x1")
        (field (name "BOM_Supplier Part") "C81276")
      )
      (libsource (lib "") (part "Unknown_975_470"))
    )
    (comp (ref "P4")
      (value "Header-Female-2.54_1x2")
      (fields
        (field (name "BOM_Manufacturer Part") "2.54-1*2PFemale")
        (field (name "BOM_Supplier Part") "C49661")
      )
      (libsource (lib "") (part "Unknown_530_415"))
    )
    (comp (ref "P5")
      (value "Header-Female-2.54_1x2")
      (fields
        (field (name "BOM_Manufacturer Part") "2.54-1*2PFemale")
        (field (name "BOM_Supplier Part") "C49661")
      )
      (libsource (lib "") (part "Unknown_660_415"))
    )
    (comp (ref "R28")
      (value "1.5K")
      (fields
        (field (name "BOM_Manufacturer Part") "AC1206JR-071K5L")
        (field (name "BOM_Supplier Part") "C144466")
      )
      (libsource (lib "") (part "AC1206JR-071K5L"))
    )
    (comp (ref "R29")
      (value "1.5K")
      (fields
        (field (name "BOM_Manufacturer Part") "AC1206JR-071K5L")
        (field (name "BOM_Supplier Part") "C144466")
      )
      (libsource (lib "") (part "AC1206JR-071K5L"))
    )
    (comp (ref "U2")
      (value "ATTINY45")
      (fields
        (field (name "BOM_Manufacturer Part") "ATTINY45-20PU")
        (field (name "BOM_Supplier Part") "C152181")
      )
      (libsource (lib "") (part "Unknown_755_120"))
    )
    (comp (ref "USB_MASTER")
      (value "A")
      (fields
        (field (name "BOM_Manufacturer Part") "A/F90degree Aparagraph 10Four feet without curling ironPBTWhite plastic6.8")
        (field (name "BOM_Supplier Part") "C42580")
      )
      (libsource (lib "") (part "Unknown_205_590"))
    )
    (comp (ref "USB_PWR")
      (value "KT-1206Red LED")
      (fields (field (name "BOM_Supplier Part") "C49018"))
      (libsource (lib "") (part "Unknown_395_670"))
    )
    (comp (ref "C1")
      (value "22uF")
      (fields
        (field (name "BOM_Manufacturer Part") "22uF 16V 4*5")
        (field (name "BOM_Supplier Part") "C43800")
      )
      (libsource (lib "") (part "22uF 16V 4*5"))
    )
    (comp (ref "C2")
      (value "22uF")
      (fields
        (field (name "BOM_Manufacturer Part") "22uF 16V 4*5")
        (field (name "BOM_Supplier Part") "C43800")
      )
      (libsource (lib "") (part "22uF 16V 4*5"))
    )
    (comp (ref "C3")
      (value "33pF")
      (fields
        (field (name "BOM_Manufacturer Part") "CC1206JKNPOCBN330")
        (field (name "BOM_Supplier Part") "C85570")
      )
      (libsource (lib "") (part "CC1206JKNPOCBN330"))
    )
    (comp (ref "C4")
      (value "33pF")
      (fields
        (field (name "BOM_Manufacturer Part") "CC1206JKNPOCBN330")
        (field (name "BOM_Supplier Part") "C85570")
      )
      (libsource (lib "") (part "CC1206JKNPOCBN330"))
    )
    (comp (ref "C5")
      (value "100nF")
      (fields
        (field (name "BOM_Manufacturer Part") "GRM319R71H104KA01D")
        (field (name "BOM_Supplier Part") "C86047")
      )
      (libsource (lib "") (part "GRM319R71H104KA01D_2"))
    )
    (comp (ref "C6")
      (value "100nF")
      (fields
        (field (name "BOM_Manufacturer Part") "GRM319R71H104KA01D")
        (field (name "BOM_Supplier Part") "C86047")
      )
      (libsource (lib "") (part "GRM319R71H104KA01D"))
    )
    (comp (ref "C7")
      (value "10uF")
      (fields
        (field (name "BOM_Manufacturer Part") "GRM31MB31A106KE18L")
        (field (name "BOM_Supplier Part") "C162498")
      )
      (libsource (lib "") (part "GRM31MB31A106KE18L"))
    )
    (comp (ref "C10")
      (value "100nF")
      (fields
        (field (name "BOM_Manufacturer Part") "GRM319R71H104KA01D")
        (field (name "BOM_Supplier Part") "C86047")
      )
      (libsource (lib "") (part "GRM319R71H104KA01D"))
    )
    (comp (ref "C11")
      (value "100nF")
      (fields
        (field (name "BOM_Manufacturer Part") "GRM319R71H104KA01D")
        (field (name "BOM_Supplier Part") "C86047")
      )
      (libsource (lib "") (part "GRM319R71H104KA01D_1"))
    )
    (comp (ref "D1")
      (value "USBLC6-2SC6")
      (fields (field (name "BOM_Supplier Part") "C7519"))
      (libsource (lib "") (part "Unknown_870_145"))
    )
    (comp (ref "R1")
      (value "1.5K")
      (fields
        (field (name "BOM_Manufacturer Part") "RTT061501FTP")
        (field (name "BOM_Supplier Part") "C104638")
      )
      (libsource (lib "") (part "RTT061501FTP"))
    )
    (comp (ref "R2")
      (value "33.2")
      (fields
        (field (name "BOM_Manufacturer Part") "RTT0633R2FTP")
        (field (name "BOM_Supplier Part") "C159577")
      )
      (libsource (lib "") (part "RTT0633R2FTP"))
    )
    (comp (ref "R3")
      (value "33.2")
      (fields
        (field (name "BOM_Manufacturer Part") "RTT0633R2FTP")
        (field (name "BOM_Supplier Part") "C159577")
      )
      (libsource (lib "") (part "RTT0633R2FTP"))
    )
    (comp (ref "R4")
      (value "33.2")
      (fields
        (field (name "BOM_Manufacturer Part") "RTT0633R2FTP")
        (field (name "BOM_Supplier Part") "C159577")
      )
      (libsource (lib "") (part "RTT0633R2FTP"))
    )
    (comp (ref "R5")
      (value "33.2")
      (fields
        (field (name "BOM_Manufacturer Part") "RTT0633R2FTP")
        (field (name "BOM_Supplier Part") "C159577")
      )
      (libsource (lib "") (part "RTT0633R2FTP"))
    )
    (comp (ref "R9")
      (value "33.2")
      (fields
        (field (name "BOM_Manufacturer Part") "RTT0633R2FTP")
        (field (name "BOM_Supplier Part") "C159577")
      )
      (libsource (lib "") (part "RTT0633R2FTP"))
    )
    (comp (ref "R10")
      (value "33.2")
      (fields
        (field (name "BOM_Manufacturer Part") "RTT0633R2FTP")
        (field (name "BOM_Supplier Part") "C159577")
      )
      (libsource (lib "") (part "RTT0633R2FTP"))
    )
    (comp (ref "R12")
      (value "15K")
      (fields
        (field (name "BOM_Manufacturer Part") "RTT06153JTP")
        (field (name "BOM_Supplier Part") "C104645")
      )
      (libsource (lib "") (part "RTT06153JTP"))
    )
    (comp (ref "R13")
      (value "1.5K")
      (fields
        (field (name "BOM_Manufacturer Part") "AC1206JR-071K5L")
        (field (name "BOM_Supplier Part") "C144466")
      )
      (libsource (lib "") (part "AC1206JR-071K5L"))
    )
    (comp (ref "R14")
      (value "15K")
      (fields
        (field (name "BOM_Manufacturer Part") "RTT06153JTP")
        (field (name "BOM_Supplier Part") "C104645")
      )
      (libsource (lib "") (part "RTT06153JTP"))
    )
    (comp (ref "R15")
      (value "15K")
      (fields
        (field (name "BOM_Manufacturer Part") "RTT06153JTP")
        (field (name "BOM_Supplier Part") "C104645")
      )
      (libsource (lib "") (part "RTT06153JTP"))
    )
    (comp (ref "R16")
      (value "15K")
      (fields
        (field (name "BOM_Manufacturer Part") "RTT06153JTP")
        (field (name "BOM_Supplier Part") "C104645")
      )
      (libsource (lib "") (part "RTT06153JTP"))
    )
    (comp (ref "R17")
      (value "33.2")
      (fields
        (field (name "BOM_Manufacturer Part") "RTT0633R2FTP")
        (field (name "BOM_Supplier Part") "C159577")
      )
      (libsource (lib "") (part "RTT0633R2FTP"))
    )
    (comp (ref "R18")
      (value "33.2")
      (fields
        (field (name "BOM_Manufacturer Part") "RTT0633R2FTP")
        (field (name "BOM_Supplier Part") "C159577")
      )
      (libsource (lib "") (part "RTT0633R2FTP"))
    )
    (comp (ref "R19")
      (value "15K")
      (fields
        (field (name "BOM_Manufacturer Part") "RTT06153JTP")
        (field (name "BOM_Supplier Part") "C104645")
      )
      (libsource (lib "") (part "RTT06153JTP"))
    )
    (comp (ref "R20")
      (value "15K")
      (fields
        (field (name "BOM_Manufacturer Part") "RTT06153JTP")
        (field (name "BOM_Supplier Part") "C104645")
      )
      (libsource (lib "") (part "RTT06153JTP"))
    )
    (comp (ref "R35")
      (value "1.5K")
      (fields
        (field (name "BOM_Manufacturer Part") "AC1206JR-071K5L")
        (field (name "BOM_Supplier Part") "C144466")
      )
      (libsource (lib "") (part "AC1206JR-071K5L"))
    )
    (comp (ref "R38")
      (value "1.5K")
      (fields
        (field (name "BOM_Manufacturer Part") "AC1206JR-071K5L")
        (field (name "BOM_Supplier Part") "C144466")
      )
      (libsource (lib "") (part "AC1206JR-071K5L"))
    )
    (comp (ref "U4")
      (value "TUSB2046BVFR")
      (fields (field (name "BOM_Manufacturer Part") "?"))
      (libsource (lib "") (part "Unknown_435_275"))
    )
    (comp (ref "U5")
      (value "SE8117T33HF")
      (fields (field (name "BOM_Supplier Part") "C115002"))
      (libsource (lib "") (part "Unknown_145_100"))
    )
    (comp (ref "USB_3V3")
      (value "KT-1206Red LED")
      (fields (field (name "BOM_Supplier Part") "C49018"))
      (libsource (lib "") (part "Unknown_140_220"))
    )
    (comp (ref "X1")
      (value "6MHz")
      (fields
        (field (name "BOM_Manufacturer Part") "6CS06000F20UCG")
        (field (name "BOM_Supplier Part") "C252308")
      )
      (libsource (lib "") (part "6CS06000F20UCG"))
    )
  )
  (nets
    (net (code "1") (name "AC2_CK") (class "Default")
      (node (ref "AC2_CK") (pin "1") (pinfunction "1_1") (pintype "input"))
      (node (ref "U1") (pin "16") (pinfunction "IO13_16") (pintype "unspecified"))
      (node (ref "U2") (pin "3") (pinfunction "PB4_3") (pintype "bidirectional"))
    )
    (net (code "2") (name "AC2_DT") (class "Default")
      (node (ref "AC2_DT") (pin "1") (pinfunction "1_1") (pintype "input"))
      (node (ref "U1") (pin "23") (pinfunction "IO15_23") (pintype "unspecified"))
      (node (ref "U2") (pin "6") (pinfunction "PB1_6") (pintype "bidirectional"))
    )
    (net (code "3") (name "ALT_5V") (class "Default")
      (node (ref "C20") (pin "1") (pinfunction "1_1") (pintype "input"))
      (node (ref "C35") (pin "1") (pinfunction "1_1") (pintype "unspecified"))
      (node (ref "C36") (pin "2") (pinfunction "2_2") (pintype "unspecified"))
      (node (ref "C37") (pin "2") (pinfunction "2_2") (pintype "unspecified"))
      (node (ref "P4") (pin "1") (pinfunction "1_1") (pintype "input"))
      (node (ref "P5") (pin "1") (pinfunction "1_1") (pintype "input"))
      (node (ref "TOP_HEADER") (pin "11") (pinfunction "11_11") (pintype "input"))
      (node (ref "U13") (pin "13") (pinfunction "PVDD_13") (pintype "unspecified"))
      (node (ref "U13") (pin "4") (pinfunction "PVDD_4") (pintype "unspecified"))
      (node (ref "U13") (pin "6") (pinfunction "VDD_6") (pintype "unspecified"))
      (node (ref "U6") (pin "3") (pinfunction "IN_3") (pintype "unspecified"))
    )
    (net (code "4") (name "CEC") (class "Default")
      (node (ref "CEC") (pin "1") (pinfunction "1_1") (pintype "input"))
      (node (ref "HDMI") (pin "13") (pinfunction "CEC_13") (pintype "unspecified"))
      (node (ref "TOP_HEADER") (pin "40") (pinfunction "40_40") (pintype "input"))
    )
    (net (code "5") (name "COD_XTI") (class "Default")
      (node (ref "C29") (pin "1") (pinfunction "1_1") (pintype "input"))
      (node (ref "IC1") (pin "21") (pinfunction "XTI_21") (pintype "bidirectional"))
      (node (ref "R23") (pin "2") (pinfunction "2_2") (pintype "input"))
      (node (ref "X4") (pin "2") (pinfunction "2_2") (pintype "unspecified"))
    )
    (net (code "6") (name "COD_XTO") (class "Default")
      (node (ref "C28") (pin "1") (pinfunction "1_1") (pintype "input"))
      (node (ref "IC1") (pin "20") (pinfunction "XTO_20") (pintype "bidirectional"))
      (node (ref "R23") (pin "1") (pinfunction "1_1") (pintype "input"))
      (node (ref "X4") (pin "1") (pinfunction "1_1") (pintype "unspecified"))
    )
    (net (code "7") (name "D1+") (class "Default")
      (node (ref "R5") (pin "2") (pinfunction "2_2") (pintype "unspecified"))
      (node (ref "U7") (pin "5") (pinfunction "UD+_5") (pintype "unspecified"))
    )
    (net (code "8") (name "D1-") (class "Default")
      (node (ref "R4") (pin "2") (pinfunction "2_2") (pintype "unspecified"))
      (node (ref "U7") (pin "6") (pinfunction "UD-_6") (pintype "unspecified"))
    )
    (net (code "9") (name "D2+") (class "Default")
      (node (ref "R10") (pin "2") (pinfunction "2_2") (pintype "unspecified"))
      (node (ref "U9") (pin "5") (pinfunction "UD+_5") (pintype "unspecified"))
    )
    (net (code "10") (name "D2-") (class "Default")
      (node (ref "R9") (pin "2") (pinfunction "2_2") (pintype "unspecified"))
      (node (ref "U9") (pin "6") (pinfunction "UD-_6") (pintype "unspecified"))
    )
    (net (code "11") (name "D3+") (class "Default")
      (node (ref "R18") (pin "2") (pinfunction "2_2") (pintype "unspecified"))
      (node (ref "R21") (pin "1") (pinfunction "1_1") (pintype "unspecified"))
    )
    (net (code "12") (name "D3-") (class "Default")
      (node (ref "R17") (pin "2") (pinfunction "2_2") (pintype "unspecified"))
      (node (ref "R22") (pin "2") (pinfunction "2_2") (pintype "unspecified"))
    )
    (net (code "13") (name "DDC_5V") (class "Default")
      (node (ref "HDMI") (pin "18") (pinfunction "+5V_18") (pintype "unspecified"))
      (node (ref "R28") (pin "1") (pinfunction "1_1") (pintype "unspecified"))
      (node (ref "U2") (pin "8") (pinfunction "VCC_8") (pintype "passive"))
    )
    (net (code "14") (name "DDC_SCL") (class "Default")
      (node (ref "DDC_SCL") (pin "1") (pinfunction "1_1") (pintype "input"))
      (node (ref "HDMI") (pin "15") (pinfunction "I2C-CLK_15") (pintype "unspecified"))
      (node (ref "U2") (pin "7") (pinfunction "PB2_7") (pintype "bidirectional"))
    )
    (net (code "15") (name "DDC_SDA") (class "Default")
      (node (ref "DDC_SDA") (pin "1") (pinfunction "1_1") (pintype "input"))
      (node (ref "HDMI") (pin "16") (pinfunction "I2C_DATA_16") (pintype "unspecified"))
      (node (ref "U2") (pin "5") (pinfunction "PB0_5") (pintype "bidirectional"))
    )
    (net (code "16") (name "DM1") (class "Default")
      (node (ref "R16") (pin "1") (pinfunction "1_1") (pintype "input"))
      (node (ref "R4") (pin "1") (pinfunction "1_1") (pintype "unspecified"))
      (node (ref "U4") (pin "11") (pinfunction "DM1_11") (pintype "bidirectional"))
    )
    (net (code "17") (name "DM2") (class "Default")
      (node (ref "R12") (pin "1") (pinfunction "1_1") (pintype "input"))
      (node (ref "R9") (pin "1") (pinfunction "1_1") (pintype "unspecified"))
      (node (ref "U4") (pin "15") (pinfunction "DM2_15") (pintype "bidirectional"))
    )
    (net (code "18") (name "DM3") (class "Default")
      (node (ref "R17") (pin "1") (pinfunction "1_1") (pintype "unspecified"))
      (node (ref "R19") (pin "1") (pinfunction "1_1") (pintype "input"))
      (node (ref "U4") (pin "19") (pinfunction "DM3_19") (pintype "bidirectional"))
    )
    (net (code "19") (name "DP1") (class "Default")
      (node (ref "R15") (pin "2") (pinfunction "2_2") (pintype "input"))
      (node (ref "R5") (pin "1") (pinfunction "1_1") (pintype "unspecified"))
      (node (ref "U4") (pin "12") (pinfunction "DP1_12") (pintype "bidirectional"))
    )
    (net (code "20") (name "DP2") (class "Default")
      (node (ref "R10") (pin "1") (pinfunction "1_1") (pintype "unspecified"))
      (node (ref "R14") (pin "2") (pinfunction "2_2") (pintype "input"))
      (node (ref "U4") (pin "16") (pinfunction "DP2_16") (pintype "bidirectional"))
    )
    (net (code "21") (name "DP3") (class "Default")
      (node (ref "R18") (pin "1") (pinfunction "1_1") (pintype "unspecified"))
      (node (ref "R20") (pin "2") (pinfunction "2_2") (pintype "input"))
      (node (ref "U4") (pin "20") (pinfunction "DP3_20") (pintype "bidirectional"))
    )
    (net (code "22") (name "ESP_3V3") (class "Default")
      (node (ref "C18") (pin "1") (pinfunction "1_1") (pintype "unspecified"))
      (node (ref "C19") (pin "1") (pinfunction "1_1") (pintype "input"))
      (node (ref "C21") (pin "1") (pinfunction "1_1") (pintype "unspecified"))
      (node (ref "R32") (pin "1") (pinfunction "1_1") (pintype "unspecified"))
      (node (ref "R33") (pin "1") (pinfunction "1_1") (pintype "unspecified"))
      (node (ref "R8") (pin "2") (pinfunction "2_2") (pintype "input"))
      (node (ref "U1") (pin "2") (pinfunction "3V3_2") (pintype "unspecified"))
      (node (ref "U6") (pin "2") (pinfunction "OUT_2") (pintype "unspecified"))
      (node (ref "U6") (pin "4") (pinfunction "OUT_4") (pintype "unspecified"))
    )
    (net (code "23") (name "ESP_AUDIO_SELECT") (class "Default")
      (node (ref "U1") (pin "8") (pinfunction "IO32_8") (pintype "unspecified"))
      (node (ref "U11") (pin "1") (pinfunction "Se1_1") (pintype "unspecified"))
    )
    (net (code "24") (name "ESP_DTR") (class "Default")
      (node (ref "Q2") (pin "2") (pinfunction "E_2") (pintype "input"))
      (node (ref "R25") (pin "1") (pinfunction "1_1") (pintype "input"))
      (node (ref "U7") (pin "13") (pinfunction "DTR#_13") (pintype "unspecified"))
    )
    (net (code "25") (name "ESP_EN") (class "Default")
      (node (ref "C22") (pin "1") (pinfunction "1_1") (pintype "unspecified"))
      (node (ref "Q1") (pin "3") (pinfunction "C_3") (pintype "input"))
      (node (ref "R8") (pin "1") (pinfunction "1_1") (pintype "input"))
      (node (ref "U1") (pin "3") (pinfunction "EN_3") (pintype "unspecified"))
    )
    (net (code "26") (name "ESP_F_CS") (class "Default")
      (node (ref "U1") (pin "28") (pinfunction "IO17_28") (pintype "unspecified"))
      (node (ref "U8") (pin "2") (pinfunction "2Y0_2") (pintype "unspecified"))
    )
    (net (code "27") (name "ESP_F_CTRL") (class "Default")
      (node (ref "U1") (pin "37") (pinfunction "IO23_37") (pintype "unspecified"))
      (node (ref "U10") (pin "10") (pinfunction "S2_10") (pintype "unspecified"))
      (node (ref "U10") (pin "11") (pinfunction "S1_11") (pintype "unspecified"))
      (node (ref "U10") (pin "9") (pinfunction "S3_9") (pintype "unspecified"))
      (node (ref "U8") (pin "10") (pinfunction "S2_10") (pintype "unspecified"))
      (node (ref "U8") (pin "11") (pinfunction "S1_11") (pintype "unspecified"))
      (node (ref "U8") (pin "9") (pinfunction "S3_9") (pintype "unspecified"))
    )
    (net (code "28") (name "ESP_F_HOLD") (class "Default")
      (node (ref "U1") (pin "30") (pinfunction "IO18_30") (pintype "unspecified"))
      (node (ref "U8") (pin "5") (pinfunction "3Y0_5") (pintype "unspecified"))
    )
    (net (code "29") (name "ESP_F_SCK") (class "Default")
      (node (ref "U1") (pin "31") (pinfunction "IO19_31") (pintype "unspecified"))
      (node (ref "U10") (pin "2") (pinfunction "2Y0_2") (pintype "unspecified"))
    )
    (net (code "30") (name "ESP_F_SI") (class "Default")
      (node (ref "U1") (pin "33") (pinfunction "IO21_33") (pintype "unspecified"))
      (node (ref "U10") (pin "5") (pinfunction "3Y0_5") (pintype "unspecified"))
    )
    (net (code "31") (name "ESP_F_SO") (class "Default")
      (node (ref "U1") (pin "27") (pinfunction "IO16_27") (pintype "unspecified"))
      (node (ref "U8") (pin "12") (pinfunction "1Y0_12") (pintype "unspecified"))
    )
    (net (code "32") (name "ESP_F_WP") (class "Default")
      (node (ref "U1") (pin "36") (pinfunction "IO22_36") (pintype "unspecified"))
      (node (ref "U10") (pin "12") (pinfunction "1Y0_12") (pintype "unspecified"))
    )
    (net (code "33") (name "ESP_IO0") (class "Default")
      (node (ref "Q2") (pin "3") (pinfunction "C_3") (pintype "input"))
      (node (ref "U1") (pin "25") (pinfunction "IO0_25") (pintype "unspecified"))
    )
    (net (code "34") (name "ESP_RTS") (class "Default")
      (node (ref "Q1") (pin "2") (pinfunction "E_2") (pintype "input"))
      (node (ref "R7") (pin "1") (pinfunction "1_1") (pintype "input"))
      (node (ref "U7") (pin "14") (pinfunction "RTS#_14") (pintype "unspecified"))
    )
    (net (code "35") (name "ESP_RX") (class "Default")
      (node (ref "U1") (pin "34") (pinfunction "RXD0_34") (pintype "unspecified"))
      (node (ref "U7") (pin "2") (pinfunction "TXD_2") (pintype "unspecified"))
    )
    (net (code "36") (name "ESP_RX2") (class "Default")
      (node (ref "U1") (pin "11") (pinfunction "IO26_11") (pintype "unspecified"))
      (node (ref "U9") (pin "2") (pinfunction "TXD_2") (pintype "unspecified"))
    )
    (net (code "37") (name "ESP_TX") (class "Default")
      (node (ref "U1") (pin "35") (pinfunction "TXD0_35") (pintype "unspecified"))
      (node (ref "U7") (pin "3") (pinfunction "RXD_3") (pintype "unspecified"))
    )
    (net (code "38") (name "ESP_TX2") (class "Default")
      (node (ref "U1") (pin "12") (pinfunction "IO27_12") (pintype "unspecified"))
      (node (ref "U9") (pin "3") (pinfunction "RXD_3") (pintype "unspecified"))
    )
    (net (code "39") (name "FPGA_BCK") (class "Default")
      (node (ref "TOP_HEADER") (pin "7") (pinfunction "7_7") (pintype "input"))
      (node (ref "U12") (pin "1") (pinfunction "BCK_1") (pintype "unspecified"))
    )
    (net (code "40") (name "FPGA_DATA") (class "Default")
      (node (ref "TOP_HEADER") (pin "10") (pinfunction "10_10") (pintype "input"))
      (node (ref "U12") (pin "2") (pinfunction "DATA_2") (pintype "unspecified"))
    )
    (net (code "41") (name "FPGA_F_CS") (class "Default")
      (node (ref "TOP_HEADER") (pin "5") (pinfunction "5_5") (pintype "input"))
      (node (ref "U8") (pin "1") (pinfunction "2Y1_1") (pintype "unspecified"))
    )
    (net (code "42") (name "FPGA_F_HOLD") (class "Default")
      (node (ref "TOP_HEADER") (pin "3") (pinfunction "3_3") (pintype "input"))
      (node (ref "U8") (pin "3") (pinfunction "3Y1_3") (pintype "unspecified"))
    )
    (net (code "43") (name "FPGA_F_SCK") (class "Default")
      (node (ref "TOP_HEADER") (pin "1") (pinfunction "1_1") (pintype "input"))
      (node (ref "U10") (pin "1") (pinfunction "2Y1_1") (pintype "unspecified"))
    )
    (net (code "44") (name "FPGA_F_SI") (class "Default")
      (node (ref "TOP_HEADER") (pin "4") (pinfunction "4_4") (pintype "input"))
      (node (ref "U10") (pin "3") (pinfunction "3Y1_3") (pintype "unspecified"))
    )
    (net (code "45") (name "FPGA_F_SO") (class "Default")
      (node (ref "TOP_HEADER") (pin "6") (pinfunction "6_6") (pintype "input"))
      (node (ref "U8") (pin "13") (pinfunction "1Y1_13") (pintype "unspecified"))
    )
    (net (code "46") (name "FPGA_F_WP") (class "Default")
      (node (ref "TOP_HEADER") (pin "2") (pinfunction "2_2") (pintype "input"))
      (node (ref "U10") (pin "13") (pinfunction "1Y1_13") (pintype "unspecified"))
    )
    (net (code "47") (name "FPGA_LEFT") (class "Default")
      (node (ref "U11") (pin "3") (pinfunction "Dp2_3") (pintype "unspecified"))
      (node (ref "U12") (pin "7") (pinfunction "VOUTL_7") (pintype "unspecified"))
    )
    (net (code "48") (name "FPGA_LRCK") (class "Default")
      (node (ref "TOP_HEADER") (pin "9") (pinfunction "9_9") (pintype "input"))
      (node (ref "U12") (pin "3") (pinfunction "LRCK_3") (pintype "unspecified"))
    )
    (net (code "49") (name "FPGA_RIGHT") (class "Default")
      (node (ref "U11") (pin "7") (pinfunction "Dn2_7") (pintype "unspecified"))
      (node (ref "U12") (pin "8") (pinfunction "VOUTR_8") (pintype "unspecified"))
    )
    (net (code "50") (name "FPGA_SCK") (class "Default")
      (node (ref "TOP_HEADER") (pin "8") (pinfunction "8_8") (pintype "input"))
      (node (ref "U12") (pin "16") (pinfunction "SCK_16") (pintype "unspecified"))
    )
    (net (code "51") (name "GND") (class "Default")
      (node (ref "BOTTOM_HEADER") (pin "10") (pinfunction "10_10") (pintype "input"))
      (node (ref "BOTTOM_HEADER") (pin "17") (pinfunction "17_17") (pintype "input"))
      (node (ref "BOTTOM_HEADER") (pin "18") (pinfunction "18_18") (pintype "input"))
      (node (ref "BOTTOM_HEADER") (pin "25") (pinfunction "25_25") (pintype "input"))
      (node (ref "BOTTOM_HEADER") (pin "26") (pinfunction "26_26") (pintype "input"))
      (node (ref "BOTTOM_HEADER") (pin "33") (pinfunction "33_33") (pintype "input"))
      (node (ref "BOTTOM_HEADER") (pin "34") (pinfunction "34_34") (pintype "input"))
      (node (ref "BOTTOM_HEADER") (pin "7") (pinfunction "7_7") (pintype "input"))
      (node (ref "BOTTOM_HEADER") (pin "8") (pinfunction "8_8") (pintype "input"))
      (node (ref "BOTTOM_HEADER") (pin "9") (pinfunction "9_9") (pintype "input"))
      (node (ref "C1") (pin "2") (pinfunction "2_2") (pintype "input"))
      (node (ref "C10") (pin "2") (pinfunction "2_2") (pintype "unspecified"))
      (node (ref "C11") (pin "2") (pinfunction "2_2") (pintype "unspecified"))
      (node (ref "C12") (pin "1") (pinfunction "1_1") (pintype "unspecified"))
      (node (ref "C13") (pin "1") (pinfunction "1_1") (pintype "unspecified"))
      (node (ref "C14") (pin "1") (pinfunction "1_1") (pintype "unspecified"))
      (node (ref "C15") (pin "1") (pinfunction "1_1") (pintype "unspecified"))
      (node (ref "C16") (pin "2") (pinfunction "2_2") (pintype "unspecified"))
      (node (ref "C17") (pin "2") (pinfunction "2_2") (pintype "unspecified"))
      (node (ref "C18") (pin "2") (pinfunction "2_2") (pintype "unspecified"))
      (node (ref "C19") (pin "2") (pinfunction "2_2") (pintype "input"))
      (node (ref "C2") (pin "2") (pinfunction "2_2") (pintype "input"))
      (node (ref "C20") (pin "2") (pinfunction "2_2") (pintype "input"))
      (node (ref "C21") (pin "2") (pinfunction "2_2") (pintype "unspecified"))
      (node (ref "C22") (pin "2") (pinfunction "2_2") (pintype "unspecified"))
      (node (ref "C23") (pin "1") (pinfunction "1_1") (pintype "input"))
      (node (ref "C24") (pin "1") (pinfunction "1_1") (pintype "input"))
      (node (ref "C25") (pin "1") (pinfunction "1_1") (pintype "input"))
      (node (ref "C26") (pin "1") (pinfunction "1_1") (pintype "input"))
      (node (ref "C27") (pin "2") (pinfunction "2_2") (pintype "unspecified"))
      (node (ref "C28") (pin "2") (pinfunction "2_2") (pintype "input"))
      (node (ref "C29") (pin "2") (pinfunction "2_2") (pintype "input"))
      (node (ref "C3") (pin "2") (pinfunction "2_2") (pintype "input"))
      (node (ref "C31") (pin "1") (pinfunction "1_1") (pintype "unspecified"))
      (node (ref "C32") (pin "2") (pinfunction "2_2") (pintype "unspecified"))
      (node (ref "C33") (pin "2") (pinfunction "2_2") (pintype "unspecified"))
      (node (ref "C34") (pin "2") (pinfunction "2_2") (pintype "unspecified"))
      (node (ref "C35") (pin "2") (pinfunction "2_2") (pintype "unspecified"))
      (node (ref "C36") (pin "1") (pinfunction "1_1") (pintype "unspecified"))
      (node (ref "C37") (pin "1") (pinfunction "1_1") (pintype "unspecified"))
      (node (ref "C38") (pin "1") (pinfunction "1_1") (pintype "unspecified"))
      (node (ref "C4") (pin "2") (pinfunction "2_2") (pintype "input"))
      (node (ref "C40") (pin "1") (pinfunction "1_1") (pintype "unspecified"))
      (node (ref "C43") (pin "1") (pinfunction "1_1") (pintype "unspecified"))
      (node (ref "C5") (pin "1") (pinfunction "1_1") (pintype "unspecified"))
      (node (ref "C6") (pin "2") (pinfunction "2_2") (pintype "unspecified"))
      (node (ref "C7") (pin "1") (pinfunction "1_1") (pintype "unspecified"))
      (node (ref "C8") (pin "2") (pinfunction "2_2") (pintype "unspecified"))
      (node (ref "C9") (pin "2") (pinfunction "2_2") (pintype "unspecified"))
      (node (ref "D1") (pin "2") (pinfunction "2_2") (pintype "input"))
      (node (ref "DDC_PWR") (pin "2") (pinfunction "K_2") (pintype "unspecified"))
      (node (ref "ESP_PWR") (pin "2") (pinfunction "K_2") (pintype "unspecified"))
      (node (ref "GND") (pin "1") (pinfunction "1_1") (pintype "input"))
      (node (ref "GNDX") (pin "1") (pinfunction "1_1") (pintype "input"))
      (node (ref "GNDXX") (pin "1") (pinfunction "1_1") (pintype "input"))
      (node (ref "HDMI") (pin "11") (pinfunction "CK_SHIELD_11") (pintype "unspecified"))
      (node (ref "HDMI") (pin "17") (pinfunction "GND_17") (pintype "unspecified"))
      (node (ref "HDMI") (pin "2") (pinfunction "D2_SHIELD_2") (pintype "unspecified"))
      (node (ref "HDMI") (pin "5") (pinfunction "D1_SHIELD_5") (pintype "unspecified"))
      (node (ref "HDMI") (pin "8") (pinfunction "D0_SHIELD_8") (pintype "unspecified"))
      (node (ref "IC1") (pin "11") (pinfunction "AGNDC_11") (pintype "bidirectional"))
      (node (ref "IC1") (pin "18") (pinfunction "AGNDP_18") (pintype "bidirectional"))
      (node (ref "IC1") (pin "22") (pinfunction "AGNDX_22") (pintype "bidirectional"))
      (node (ref "IC1") (pin "26") (pinfunction "DGND_26") (pintype "bidirectional"))
      (node (ref "IC1") (pin "4") (pinfunction "GNDU_4") (pintype "bidirectional"))
      (node (ref "IS37SML01G1") (pin "10") (pinfunction "VSS_10") (pintype "unspecified"))
      (node (ref "MATRIX_OUT") (pin "16") (pinfunction "GND_16") (pintype "input"))
      (node (ref "MATRIX_OUT") (pin "4") (pinfunction "GND_4") (pintype "input"))
      (node (ref "P1") (pin "2") (pinfunction "2_2") (pintype "input"))
      (node (ref "P4") (pin "2") (pinfunction "2_2") (pintype "input"))
      (node (ref "P5") (pin "2") (pinfunction "2_2") (pintype "input"))
      (node (ref "R12") (pin "2") (pinfunction "2_2") (pintype "input"))
      (node (ref "R14") (pin "1") (pinfunction "1_1") (pintype "input"))
      (node (ref "R15") (pin "1") (pinfunction "1_1") (pintype "input"))
      (node (ref "R16") (pin "2") (pinfunction "2_2") (pintype "input"))
      (node (ref "R19") (pin "2") (pinfunction "2_2") (pintype "input"))
      (node (ref "R20") (pin "1") (pinfunction "1_1") (pintype "input"))
      (node (ref "R27") (pin "2") (pinfunction "2_2") (pintype "input"))
      (node (ref "TOP_HEADER") (pin "12") (pinfunction "12_12") (pintype "input"))
      (node (ref "TOP_HEADER") (pin "30") (pinfunction "30_30") (pintype "input"))
      (node (ref "U1") (pin "1") (pinfunction "GND_1") (pintype "unspecified"))
      (node (ref "U1") (pin "15") (pinfunction "GND_15") (pintype "unspecified"))
      (node (ref "U1") (pin "38") (pinfunction "GND_38") (pintype "unspecified"))
      (node (ref "U1") (pin "39") (pinfunction "EP_39") (pintype "unspecified"))
      (node (ref "U10") (pin "6") (pinfunction "/E_6") (pintype "unspecified"))
      (node (ref "U10") (pin "7") (pinfunction "VEE_7") (pintype "unspecified"))
      (node (ref "U10") (pin "8") (pinfunction "GND_8") (pintype "unspecified"))
      (node (ref "U11") (pin "5") (pinfunction "GND_5") (pintype "unspecified"))
      (node (ref "U11") (pin "9") (pinfunction "OEb_9") (pintype "unspecified"))
      (node (ref "U12") (pin "12") (pinfunction "TEST_12") (pintype "unspecified"))
      (node (ref "U12") (pin "13") (pinfunction "DEMP_13") (pintype "unspecified"))
      (node (ref "U12") (pin "14") (pinfunction "MUTE_14") (pintype "unspecified"))
      (node (ref "U12") (pin "15") (pinfunction "FMT_15") (pintype "unspecified"))
      (node (ref "U12") (pin "4") (pinfunction "DGND_4") (pintype "unspecified"))
      (node (ref "U12") (pin "9") (pinfunction "AGND_9") (pintype "unspecified"))
      (node (ref "U13") (pin "11") (pinfunction "GND_11") (pintype "unspecified"))
      (node (ref "U13") (pin "15") (pinfunction "PGND_15") (pintype "unspecified"))
      (node (ref "U13") (pin "2") (pinfunction "PGND_2") (pintype "unspecified"))
      (node (ref "U14") (pin "2") (pinfunction "GND_2") (pintype "bidirectional"))
      (node (ref "U2") (pin "4") (pinfunction "GND_4") (pintype "passive"))
      (node (ref "U4") (pin "27") (pinfunction "TSTPLL48MCLK_27") (pintype "unspecified"))
      (node (ref "U4") (pin "28") (pinfunction "GND_28") (pintype "passive"))
      (node (ref "U4") (pin "31") (pinfunction "TSTMODE_31") (pintype "unspecified"))
      (node (ref "U4") (pin "6") (pinfunction "EEDATAGANGED_6") (pintype "bidirectional"))
      (node (ref "U4") (pin "7") (pinfunction "GND_7") (pintype "passive"))
      (node (ref "U4") (pin "8") (pinfunction "BUSPWR_8") (pintype "unspecified"))
      (node (ref "U5") (pin "1") (pinfunction "ADJ/GND_1") (pintype "unspecified"))
      (node (ref "U6") (pin "1") (pinfunction "ADJ/GND_1") (pintype "unspecified"))
      (node (ref "U7") (pin "1") (pinfunction "GND_1") (pintype "unspecified"))
      (node (ref "U8") (pin "6") (pinfunction "/E_6") (pintype "unspecified"))
      (node (ref "U8") (pin "7") (pinfunction "VEE_7") (pintype "unspecified"))
      (node (ref "U8") (pin "8") (pinfunction "GND_8") (pintype "unspecified"))
      (node (ref "U9") (pin "1") (pinfunction "GND_1") (pintype "unspecified"))
      (node (ref "USB_3V3") (pin "2") (pinfunction "K_2") (pintype "unspecified"))
      (node (ref "USB_MASTER") (pin "4") (pinfunction "GND_4") (pintype "input"))
      (node (ref "USB_PWR") (pin "2") (pinfunction "K_2") (pintype "unspecified"))
    )
    (net (code "52") (name "HDMI_B+") (class "Default")
      (node (ref "HDMI") (pin "7") (pinfunction "D0+_7") (pintype "unspecified"))
      (node (ref "TOP_HEADER") (pin "33") (pinfunction "33_33") (pintype "input"))
    )
    (net (code "53") (name "HDMI_B-") (class "Default")
      (node (ref "HDMI") (pin "9") (pinfunction "D0-_9") (pintype "unspecified"))
      (node (ref "TOP_HEADER") (pin "34") (pinfunction "34_34") (pintype "input"))
    )
    (net (code "54") (name "HDMI_CK+") (class "Default")
      (node (ref "HDMI") (pin "10") (pinfunction "CK+_10") (pintype "unspecified"))
      (node (ref "TOP_HEADER") (pin "37") (pinfunction "37_37") (pintype "input"))
    )
    (net (code "55") (name "HDMI_CK-") (class "Default")
      (node (ref "HDMI") (pin "12") (pinfunction "CK-_12") (pintype "unspecified"))
      (node (ref "TOP_HEADER") (pin "38") (pinfunction "38_38") (pintype "input"))
    )
    (net (code "56") (name "HDMI_G+") (class "Default")
      (node (ref "HDMI") (pin "4") (pinfunction "D1+_4") (pintype "unspecified"))
      (node (ref "TOP_HEADER") (pin "27") (pinfunction "27_27") (pintype "input"))
    )
    (net (code "57") (name "HDMI_G-") (class "Default")
      (node (ref "HDMI") (pin "6") (pinfunction "D1-_6") (pintype "unspecified"))
      (node (ref "TOP_HEADER") (pin "28") (pinfunction "28_28") (pintype "input"))
    )
    (net (code "58") (name "HDMI_R+") (class "Default")
      (node (ref "HDMI") (pin "1") (pinfunction "D2+_1") (pintype "unspecified"))
      (node (ref "TOP_HEADER") (pin "23") (pinfunction "23_23") (pintype "input"))
    )
    (net (code "59") (name "HDMI_R-") (class "Default")
      (node (ref "HDMI") (pin "3") (pinfunction "D2-_3") (pintype "unspecified"))
      (node (ref "TOP_HEADER") (pin "24") (pinfunction "24_24") (pintype "input"))
    )
    (net (code "60") (name "HEC") (class "Default")
      (node (ref "HDMI") (pin "14") (pinfunction "HEC_14") (pintype "unspecified"))
      (node (ref "HEC") (pin "1") (pinfunction "1_1") (pintype "input"))
      (node (ref "TOP_HEADER") (pin "39") (pinfunction "39_39") (pintype "input"))
    )
    (net (code "61") (name "HOT_PLUG") (class "Default")
      (node (ref "HDMI") (pin "19") (pinfunction "HOT_PLUG_DET_19") (pintype "unspecified"))
      (node (ref "HOT_PLUG") (pin "1") (pinfunction "1_1") (pintype "input"))
      (node (ref "U2") (pin "2") (pinfunction "PB3_2") (pintype "bidirectional"))
    )
    (net (code "62") (name "MIC_L") (class "Default")
      (node (ref "C45") (pin "1") (pinfunction "1_1") (pintype "unspecified"))
      (node (ref "IC1") (pin "12") (pinfunction "VIN_L_12") (pintype "bidirectional"))
      (node (ref "IC1") (pin "13") (pinfunction "VIN_R_13") (pintype "bidirectional"))
      (node (ref "R34") (pin "2") (pinfunction "2_2") (pintype "unspecified"))
      (node (ref "U14") (pin "4") (pinfunction "OUT_4") (pintype "bidirectional"))
    )
    (net (code "63") (name "MIC_L+") (class "Default")
      (node (ref "C39") (pin "2") (pinfunction "2_2") (pintype "unspecified"))
      (node (ref "P1") (pin "1") (pinfunction "1_1") (pintype "input"))
      (node (ref "R30") (pin "1") (pinfunction "1_1") (pintype "input"))
    )
    (net (code "64") (name "MUTE") (class "Default")
      (node (ref "U1") (pin "9") (pinfunction "IO33_9") (pintype "unspecified"))
      (node (ref "U13") (pin "5") (pinfunction "MUTE_5") (pintype "unspecified"))
    )
    (net (code "65") (name "M_A") (class "Default")
      (node (ref "BOTTOM_HEADER") (pin "30") (pinfunction "30_30") (pintype "input"))
      (node (ref "MATRIX_OUT") (pin "9") (pinfunction "A_9") (pintype "input"))
    )
    (net (code "66") (name "M_B") (class "Default")
      (node (ref "BOTTOM_HEADER") (pin "29") (pinfunction "29_29") (pintype "input"))
      (node (ref "MATRIX_OUT") (pin "10") (pinfunction "B_10") (pintype "input"))
    )
    (net (code "67") (name "M_B0") (class "Default")
      (node (ref "BOTTOM_HEADER") (pin "20") (pinfunction "20_20") (pintype "input"))
      (node (ref "MATRIX_OUT") (pin "3") (pinfunction "B0_3") (pintype "input"))
    )
    (net (code "68") (name "M_B1") (class "Default")
      (node (ref "BOTTOM_HEADER") (pin "24") (pinfunction "24_24") (pintype "input"))
      (node (ref "MATRIX_OUT") (pin "7") (pinfunction "B1_7") (pintype "input"))
    )
    (net (code "69") (name "M_C") (class "Default")
      (node (ref "BOTTOM_HEADER") (pin "32") (pinfunction "32_32") (pintype "input"))
      (node (ref "MATRIX_OUT") (pin "11") (pinfunction "C_11") (pintype "input"))
    )
    (net (code "70") (name "M_CLK") (class "Default")
      (node (ref "BOTTOM_HEADER") (pin "38") (pinfunction "38_38") (pintype "input"))
      (node (ref "MATRIX_OUT") (pin "13") (pinfunction "CLK_13") (pintype "input"))
    )
    (net (code "71") (name "M_D") (class "Default")
      (node (ref "BOTTOM_HEADER") (pin "31") (pinfunction "31_31") (pintype "input"))
      (node (ref "MATRIX_OUT") (pin "12") (pinfunction "D_12") (pintype "input"))
    )
    (net (code "72") (name "M_E") (class "Default")
      (node (ref "BOTTOM_HEADER") (pin "27") (pinfunction "27_27") (pintype "input"))
      (node (ref "MATRIX_OUT") (pin "8") (pinfunction "E_8") (pintype "input"))
    )
    (net (code "73") (name "M_G0") (class "Default")
      (node (ref "BOTTOM_HEADER") (pin "21") (pinfunction "21_21") (pintype "input"))
      (node (ref "MATRIX_OUT") (pin "2") (pinfunction "G0_2") (pintype "input"))
    )
    (net (code "74") (name "M_G1") (class "Default")
      (node (ref "BOTTOM_HEADER") (pin "23") (pinfunction "23_23") (pintype "input"))
      (node (ref "MATRIX_OUT") (pin "6") (pinfunction "G1_6") (pintype "input"))
    )
    (net (code "75") (name "M_LATCH") (class "Default")
      (node (ref "BOTTOM_HEADER") (pin "39") (pinfunction "39_39") (pintype "input"))
      (node (ref "MATRIX_OUT") (pin "14") (pinfunction "LAT_14") (pintype "input"))
    )
    (net (code "76") (name "M_OE") (class "Default")
      (node (ref "BOTTOM_HEADER") (pin "40") (pinfunction "40_40") (pintype "input"))
      (node (ref "MATRIX_OUT") (pin "15") (pinfunction "OE_15") (pintype "input"))
    )
    (net (code "77") (name "M_R0") (class "Default")
      (node (ref "BOTTOM_HEADER") (pin "16") (pinfunction "16_16") (pintype "input"))
      (node (ref "MATRIX_OUT") (pin "1") (pinfunction "R0_1") (pintype "input"))
    )
    (net (code "78") (name "M_R1") (class "Default")
      (node (ref "BOTTOM_HEADER") (pin "22") (pinfunction "22_22") (pintype "input"))
      (node (ref "MATRIX_OUT") (pin "5") (pinfunction "R1_5") (pintype "input"))
    )
    (net (code "79") (name "Net-(C40-Pad2)") (class "Default")
      (node (ref "C40") (pin "2") (pinfunction "2_2") (pintype "unspecified"))
      (node (ref "R30") (pin "2") (pinfunction "2_2") (pintype "input"))
      (node (ref "R31") (pin "1") (pinfunction "1_1") (pintype "input"))
    )
    (net (code "80") (name "Net-(C43-Pad2)") (class "Default")
      (node (ref "C43") (pin "2") (pinfunction "2_2") (pintype "unspecified"))
      (node (ref "R24") (pin "1") (pinfunction "1_1") (pintype "input"))
    )
    (net (code "81") (name "Net-(C48-Pad2)") (class "Default")
      (node (ref "C48") (pin "2") (pinfunction "2_2") (pintype "input"))
      (node (ref "R37") (pin "2") (pinfunction "2_2") (pintype "input"))
    )
    (net (code "82") (name "Net-(C49-Pad1)") (class "Default")
      (node (ref "C49") (pin "1") (pinfunction "1_1") (pintype "input"))
      (node (ref "R6") (pin "2") (pinfunction "2_2") (pintype "input"))
    )
    (net (code "83") (name "Net-(D1-Pad4)") (class "Default")
      (node (ref "D1") (pin "4") (pinfunction "4_4") (pintype "input"))
      (node (ref "R3") (pin "2") (pinfunction "2_2") (pintype "unspecified"))
    )
    (net (code "84") (name "Net-(D1-Pad6)") (class "Default")
      (node (ref "D1") (pin "6") (pinfunction "6_6") (pintype "input"))
      (node (ref "R2") (pin "2") (pinfunction "2_2") (pintype "unspecified"))
    )
    (net (code "85") (name "Net-(DDC_PWR-A)") (class "Default")
      (node (ref "DDC_PWR") (pin "1") (pinfunction "A_1") (pintype "unspecified"))
      (node (ref "R28") (pin "2") (pinfunction "2_2") (pintype "unspecified"))
    )
    (net (code "86") (name "Net-(ESP_PWR-A)") (class "Default")
      (node (ref "ESP_PWR") (pin "1") (pinfunction "A_1") (pintype "unspecified"))
      (node (ref "R32") (pin "2") (pinfunction "2_2") (pintype "unspecified"))
      (node (ref "R33") (pin "2") (pinfunction "2_2") (pintype "unspecified"))
    )
    (net (code "87") (name "Net-(IC1-D+)") (class "Default")
      (node (ref "IC1") (pin "1") (pinfunction "D+_1") (pintype "bidirectional"))
      (node (ref "R21") (pin "2") (pinfunction "2_2") (pintype "unspecified"))
    )
    (net (code "88") (name "Net-(IC1-D-)") (class "Default")
      (node (ref "IC1") (pin "2") (pinfunction "D-_2") (pintype "bidirectional"))
      (node (ref "R22") (pin "1") (pinfunction "1_1") (pintype "unspecified"))
    )
    (net (code "89") (name "Net-(IC1-VCOM)") (class "Default")
      (node (ref "C17") (pin "1") (pinfunction "1_1") (pintype "unspecified"))
      (node (ref "IC1") (pin "14") (pinfunction "VCOM_14") (pintype "bidirectional"))
    )
    (net (code "90") (name "Net-(IS37SML01G1-CS)") (class "Default")
      (node (ref "FL_CS") (pin "1") (pinfunction "1_1") (pintype "input"))
      (node (ref "IS37SML01G1") (pin "7") (pinfunction "CS_7") (pintype "unspecified"))
      (node (ref "U8") (pin "15") (pinfunction "2Z_15") (pintype "unspecified"))
    )
    (net (code "91") (name "Net-(IS37SML01G1-HOLD(IO3))") (class "Default")
      (node (ref "FL_HOLD") (pin "1") (pinfunction "1_1") (pintype "input"))
      (node (ref "IS37SML01G1") (pin "1") (pinfunction "HOLD(IO3)_1") (pintype "unspecified"))
      (node (ref "U8") (pin "4") (pinfunction "3Z_4") (pintype "unspecified"))
    )
    (net (code "92") (name "Net-(IS37SML01G1-SCK)") (class "Default")
      (node (ref "FL_SCK") (pin "1") (pinfunction "1_1") (pintype "input"))
      (node (ref "IS37SML01G1") (pin "16") (pinfunction "SCK_16") (pintype "unspecified"))
      (node (ref "U10") (pin "15") (pinfunction "2Z_15") (pintype "unspecified"))
    )
    (net (code "93") (name "Net-(IS37SML01G1-SI(IO0))") (class "Default")
      (node (ref "FL_SI") (pin "1") (pinfunction "1_1") (pintype "input"))
      (node (ref "IS37SML01G1") (pin "15") (pinfunction "SI(IO0)_15") (pintype "unspecified"))
      (node (ref "U10") (pin "4") (pinfunction "3Z_4") (pintype "unspecified"))
    )
    (net (code "94") (name "Net-(IS37SML01G1-SO(IO1))") (class "Default")
      (node (ref "FL_SO") (pin "1") (pinfunction "1_1") (pintype "input"))
      (node (ref "IS37SML01G1") (pin "8") (pinfunction "SO(IO1)_8") (pintype "unspecified"))
      (node (ref "U8") (pin "14") (pinfunction "1Z_14") (pintype "unspecified"))
    )
    (net (code "95") (name "Net-(IS37SML01G1-WP(IO2))") (class "Default")
      (node (ref "FL_WP") (pin "1") (pinfunction "1_1") (pintype "input"))
      (node (ref "IS37SML01G1") (pin "9") (pinfunction "WP(IO2)_9") (pintype "unspecified"))
      (node (ref "U10") (pin "14") (pinfunction "1Z_14") (pintype "unspecified"))
    )
    (net (code "96") (name "Net-(Q1-B)") (class "Default")
      (node (ref "Q1") (pin "1") (pinfunction "B_1") (pintype "input"))
      (node (ref "R25") (pin "2") (pinfunction "2_2") (pintype "input"))
    )
    (net (code "97") (name "Net-(Q2-B)") (class "Default")
      (node (ref "Q2") (pin "1") (pinfunction "B_1") (pintype "input"))
      (node (ref "R7") (pin "2") (pinfunction "2_2") (pintype "input"))
    )
    (net (code "98") (name "Net-(U4-DM0)") (class "Default")
      (node (ref "R2") (pin "1") (pinfunction "1_1") (pintype "unspecified"))
      (node (ref "U4") (pin "2") (pinfunction "DM0_2") (pintype "bidirectional"))
    )
    (net (code "99") (name "Net-(U4-DP0)") (class "Default")
      (node (ref "R1") (pin "2") (pinfunction "2_2") (pintype "input"))
      (node (ref "R3") (pin "1") (pinfunction "1_1") (pintype "unspecified"))
      (node (ref "U4") (pin "1") (pinfunction "DP0_1") (pintype "bidirectional"))
    )
    (net (code "100") (name "Net-(U4-XTAL1)") (class "Default")
      (node (ref "C3") (pin "1") (pinfunction "1_1") (pintype "input"))
      (node (ref "U4") (pin "30") (pinfunction "XTAL1_30") (pintype "unspecified"))
      (node (ref "X1") (pin "2") (pinfunction "OSC2_2") (pintype "input"))
    )
    (net (code "101") (name "Net-(U4-XTAL2)") (class "Default")
      (node (ref "R13") (pin "1") (pinfunction "1_1") (pintype "unspecified"))
      (node (ref "U4") (pin "29") (pinfunction "XTAL2_29") (pintype "unspecified"))
    )
    (net (code "102") (name "Net-(U7-V3)") (class "Default")
      (node (ref "C12") (pin "2") (pinfunction "2_2") (pintype "unspecified"))
      (node (ref "U7") (pin "4") (pinfunction "V3_4") (pintype "unspecified"))
    )
    (net (code "103") (name "Net-(U7-XI)") (class "Default")
      (node (ref "C24") (pin "2") (pinfunction "2_2") (pintype "input"))
      (node (ref "U7") (pin "7") (pinfunction "XI_7") (pintype "unspecified"))
      (node (ref "X2") (pin "2") (pinfunction "2_2") (pintype "unspecified"))
    )
    (net (code "104") (name "Net-(U7-XO)") (class "Default")
      (node (ref "C23") (pin "2") (pinfunction "2_2") (pintype "input"))
      (node (ref "U7") (pin "8") (pinfunction "XO_8") (pintype "unspecified"))
      (node (ref "X2") (pin "1") (pinfunction "1_1") (pintype "unspecified"))
    )
    (net (code "105") (name "Net-(U9-V3)") (class "Default")
      (node (ref "C14") (pin "2") (pinfunction "2_2") (pintype "unspecified"))
      (node (ref "U9") (pin "4") (pinfunction "V3_4") (pintype "unspecified"))
    )
    (net (code "106") (name "Net-(U9-XI)") (class "Default")
      (node (ref "C26") (pin "2") (pinfunction "2_2") (pintype "input"))
      (node (ref "U9") (pin "7") (pinfunction "XI_7") (pintype "unspecified"))
      (node (ref "X3") (pin "2") (pinfunction "2_2") (pintype "unspecified"))
    )
    (net (code "107") (name "Net-(U9-XO)") (class "Default")
      (node (ref "C25") (pin "2") (pinfunction "2_2") (pintype "input"))
      (node (ref "U9") (pin "8") (pinfunction "XO_8") (pintype "unspecified"))
      (node (ref "X3") (pin "1") (pinfunction "1_1") (pintype "unspecified"))
    )
    (net (code "108") (name "Net-(U12-VCOM)") (class "Default")
      (node (ref "C33") (pin "1") (pinfunction "1_1") (pintype "unspecified"))
      (node (ref "U12") (pin "10") (pinfunction "VCOM_10") (pintype "unspecified"))
    )
    (net (code "109") (name "Net-(U13-INL)") (class "Default")
      (node (ref "R6") (pin "1") (pinfunction "1_1") (pintype "input"))
      (node (ref "U13") (pin "7") (pinfunction "INL_7") (pintype "unspecified"))
    )
    (net (code "110") (name "Net-(U13-INR)") (class "Default")
      (node (ref "R37") (pin "1") (pinfunction "1_1") (pintype "input"))
      (node (ref "U13") (pin "10") (pinfunction "INR_10") (pintype "unspecified"))
    )
    (net (code "111") (name "Net-(U13-VREF)") (class "Default")
      (node (ref "C34") (pin "1") (pinfunction "1_1") (pintype "unspecified"))
      (node (ref "C38") (pin "2") (pinfunction "2_2") (pintype "unspecified"))
      (node (ref "U13") (pin "8") (pinfunction "VREF_8") (pintype "unspecified"))
    )
    (net (code "112") (name "Net-(U14-IN+)") (class "Default")
      (node (ref "C39") (pin "1") (pinfunction "1_1") (pintype "unspecified"))
      (node (ref "R26") (pin "1") (pinfunction "1_1") (pintype "input"))
      (node (ref "R27") (pin "1") (pinfunction "1_1") (pintype "input"))
      (node (ref "U14") (pin "1") (pinfunction "IN+_1") (pintype "bidirectional"))
    )
    (net (code "113") (name "Net-(U14-IN-)") (class "Default")
      (node (ref "C45") (pin "2") (pinfunction "2_2") (pintype "unspecified"))
      (node (ref "R24") (pin "2") (pinfunction "2_2") (pintype "input"))
      (node (ref "R34") (pin "1") (pinfunction "1_1") (pintype "unspecified"))
      (node (ref "U14") (pin "3") (pinfunction "IN-_3") (pintype "bidirectional"))
    )
    (net (code "114") (name "Net-(USB_3V3-A)") (class "Default")
      (node (ref "R35") (pin "2") (pinfunction "2_2") (pintype "unspecified"))
      (node (ref "R38") (pin "2") (pinfunction "2_2") (pintype "unspecified"))
      (node (ref "USB_3V3") (pin "1") (pinfunction "A_1") (pintype "unspecified"))
    )
    (net (code "115") (name "Net-(USB_PWR-A)") (class "Default")
      (node (ref "R29") (pin "2") (pinfunction "2_2") (pintype "unspecified"))
      (node (ref "USB_PWR") (pin "1") (pinfunction "A_1") (pintype "unspecified"))
    )
    (net (code "116") (name "Net-(X1-OSC1)") (class "Default")
      (node (ref "C4") (pin "1") (pinfunction "1_1") (pintype "input"))
      (node (ref "R13") (pin "2") (pinfunction "2_2") (pintype "unspecified"))
      (node (ref "X1") (pin "1") (pinfunction "OSC1_1") (pintype "input"))
    )
    (net (code "117") (name "PREAMP_LEFT") (class "Default")
      (node (ref "C49") (pin "2") (pinfunction "2_2") (pintype "input"))
      (node (ref "U11") (pin "4") (pinfunction "Dp_4") (pintype "unspecified"))
    )
    (net (code "118") (name "PREAMP_RIGHT") (class "Default")
      (node (ref "C48") (pin "1") (pinfunction "1_1") (pintype "input"))
      (node (ref "U11") (pin "6") (pinfunction "Dn_6") (pintype "unspecified"))
    )
    (net (code "119") (name "SPEAKER_L+") (class "Default")
      (node (ref "P2") (pin "1") (pinfunction "1_1") (pintype "input"))
      (node (ref "U13") (pin "1") (pinfunction "+OUT_L_1") (pintype "unspecified"))
    )
    (net (code "120") (name "SPEAKER_L-") (class "Default")
      (node (ref "P2") (pin "2") (pinfunction "2_2") (pintype "input"))
      (node (ref "U13") (pin "3") (pinfunction "-OUT_L_3") (pintype "unspecified"))
    )
    (net (code "121") (name "SPEAKER_R+") (class "Default")
      (node (ref "P3") (pin "1") (pinfunction "1_1") (pintype "input"))
      (node (ref "U13") (pin "16") (pinfunction "+OUT_R_16") (pintype "unspecified"))
    )
    (net (code "122") (name "SPEAKER_R-") (class "Default")
      (node (ref "P3") (pin "2") (pinfunction "2_2") (pintype "input"))
      (node (ref "U13") (pin "14") (pinfunction "-OUT_R_14") (pintype "unspecified"))
    )
    (net (code "123") (name "USB_3V3") (class "Default")
      (node (ref "C1") (pin "1") (pinfunction "1_1") (pintype "input"))
      (node (ref "C10") (pin "1") (pinfunction "1_1") (pintype "unspecified"))
      (node (ref "C13") (pin "2") (pinfunction "2_2") (pintype "unspecified"))
      (node (ref "C15") (pin "2") (pinfunction "2_2") (pintype "unspecified"))
      (node (ref "C16") (pin "1") (pinfunction "1_1") (pintype "unspecified"))
      (node (ref "C27") (pin "1") (pinfunction "1_1") (pintype "unspecified"))
      (node (ref "C5") (pin "2") (pinfunction "2_2") (pintype "unspecified"))
      (node (ref "C6") (pin "1") (pinfunction "1_1") (pintype "unspecified"))
      (node (ref "C7") (pin "2") (pinfunction "2_2") (pintype "unspecified"))
      (node (ref "C8") (pin "1") (pinfunction "1_1") (pintype "unspecified"))
      (node (ref "C9") (pin "1") (pinfunction "1_1") (pintype "unspecified"))
      (node (ref "IC1") (pin "10") (pinfunction "VCCC_10") (pintype "bidirectional"))
      (node (ref "IC1") (pin "17") (pinfunction "VCCP1_17") (pintype "bidirectional"))
      (node (ref "IC1") (pin "19") (pinfunction "VCCP2_19") (pintype "bidirectional"))
      (node (ref "IC1") (pin "23") (pinfunction "VCCX_23") (pintype "bidirectional"))
      (node (ref "IC1") (pin "27") (pinfunction "VDD_27") (pintype "bidirectional"))
      (node (ref "IC1") (pin "3") (pinfunction "VBUS_3") (pintype "bidirectional"))
      (node (ref "IS37SML01G1") (pin "2") (pinfunction "VCC_2") (pintype "unspecified"))
      (node (ref "R1") (pin "1") (pinfunction "1_1") (pintype "input"))
      (node (ref "R26") (pin "2") (pinfunction "2_2") (pintype "input"))
      (node (ref "R31") (pin "2") (pinfunction "2_2") (pintype "input"))
      (node (ref "R35") (pin "1") (pinfunction "1_1") (pintype "unspecified"))
      (node (ref "R38") (pin "1") (pinfunction "1_1") (pintype "unspecified"))
      (node (ref "U10") (pin "16") (pinfunction "VCC_16") (pintype "unspecified"))
      (node (ref "U11") (pin "10") (pinfunction "VCC_10") (pintype "unspecified"))
      (node (ref "U14") (pin "5") (pinfunction "VCC_5") (pintype "bidirectional"))
      (node (ref "U4") (pin "10") (pinfunction "OVRCUR1_10") (pintype "unspecified"))
      (node (ref "U4") (pin "14") (pinfunction "OVRCUR2_14") (pintype "unspecified"))
      (node (ref "U4") (pin "18") (pinfunction "OVRCUR3_18") (pintype "unspecified"))
      (node (ref "U4") (pin "22") (pinfunction "OVRCUR4_22") (pintype "unspecified"))
      (node (ref "U4") (pin "25") (pinfunction "VCC_25") (pintype "passive"))
      (node (ref "U4") (pin "26") (pinfunction "EXTMEM_26") (pintype "unspecified"))
      (node (ref "U4") (pin "3") (pinfunction "VCC_3") (pintype "passive"))
      (node (ref "U4") (pin "4") (pinfunction "RESET_4") (pintype "unspecified"))
      (node (ref "U5") (pin "2") (pinfunction "OUT_2") (pintype "unspecified"))
      (node (ref "U5") (pin "4") (pinfunction "OUT_4") (pintype "unspecified"))
      (node (ref "U7") (pin "16") (pinfunction "VCC_16") (pintype "unspecified"))
      (node (ref "U8") (pin "16") (pinfunction "VCC_16") (pintype "unspecified"))
      (node (ref "U9") (pin "16") (pinfunction "VCC_16") (pintype "unspecified"))
    )
    (net (code "124") (name "USB_LEFT") (class "Default")
      (node (ref "IC1") (pin "16") (pinfunction "VOUT_L_16") (pintype "bidirectional"))
      (node (ref "U11") (pin "2") (pinfunction "Dp1_2") (pintype "unspecified"))
    )
    (net (code "125") (name "USB_NEG_0") (class "Default")
      (node (ref "D1") (pin "1") (pinfunction "1_1") (pintype "input"))
      (node (ref "USB_MASTER") (pin "2") (pinfunction "D-_2") (pintype "input"))
    )
    (net (code "126") (name "USB_POS_0") (class "Default")
      (node (ref "D1") (pin "3") (pinfunction "3_3") (pintype "input"))
      (node (ref "USB_MASTER") (pin "3") (pinfunction "D+_3") (pintype "input"))
    )
    (net (code "127") (name "USB_RIGHT") (class "Default")
      (node (ref "IC1") (pin "15") (pinfunction "VOUT_R_15") (pintype "bidirectional"))
      (node (ref "U11") (pin "8") (pinfunction "Dn1_8") (pintype "unspecified"))
    )
    (net (code "128") (name "USB_VCC_0") (class "Default")
      (node (ref "C11") (pin "1") (pinfunction "1_1") (pintype "unspecified"))
      (node (ref "C2") (pin "1") (pinfunction "1_1") (pintype "input"))
      (node (ref "C31") (pin "2") (pinfunction "2_2") (pintype "unspecified"))
      (node (ref "C32") (pin "1") (pinfunction "1_1") (pintype "unspecified"))
      (node (ref "D1") (pin "5") (pinfunction "5_5") (pintype "input"))
      (node (ref "R29") (pin "1") (pinfunction "1_1") (pintype "unspecified"))
      (node (ref "U12") (pin "6") (pinfunction "VCC_6") (pintype "unspecified"))
      (node (ref "U5") (pin "3") (pinfunction "IN_3") (pintype "unspecified"))
      (node (ref "USB_MASTER") (pin "1") (pinfunction "VCC_1") (pintype "input"))
    )
    (net (code "129") (name "unconnected-(BOTTOM_HEADER-Pad1)") (class "Default")
      (node (ref "BOTTOM_HEADER") (pin "1") (pinfunction "1_1") (pintype "input+no_connect"))
    )
    (net (code "130") (name "unconnected-(BOTTOM_HEADER-Pad2)") (class "Default")
      (node (ref "BOTTOM_HEADER") (pin "2") (pinfunction "2_2") (pintype "input+no_connect"))
    )
    (net (code "131") (name "unconnected-(BOTTOM_HEADER-Pad3)") (class "Default")
      (node (ref "BOTTOM_HEADER") (pin "3") (pinfunction "3_3") (pintype "input+no_connect"))
    )
    (net (code "132") (name "unconnected-(BOTTOM_HEADER-Pad4)") (class "Default")
      (node (ref "BOTTOM_HEADER") (pin "4") (pinfunction "4_4") (pintype "input+no_connect"))
    )
    (net (code "133") (name "unconnected-(BOTTOM_HEADER-Pad5)") (class "Default")
      (node (ref "BOTTOM_HEADER") (pin "5") (pinfunction "5_5") (pintype "input+no_connect"))
    )
    (net (code "134") (name "unconnected-(BOTTOM_HEADER-Pad6)") (class "Default")
      (node (ref "BOTTOM_HEADER") (pin "6") (pinfunction "6_6") (pintype "input+no_connect"))
    )
    (net (code "135") (name "unconnected-(BOTTOM_HEADER-Pad11)") (class "Default")
      (node (ref "BOTTOM_HEADER") (pin "11") (pinfunction "11_11") (pintype "input+no_connect"))
    )
    (net (code "136") (name "unconnected-(BOTTOM_HEADER-Pad12)") (class "Default")
      (node (ref "BOTTOM_HEADER") (pin "12") (pinfunction "12_12") (pintype "input+no_connect"))
    )
    (net (code "137") (name "unconnected-(BOTTOM_HEADER-Pad13)") (class "Default")
      (node (ref "BOTTOM_HEADER") (pin "13") (pinfunction "13_13") (pintype "input+no_connect"))
    )
    (net (code "138") (name "unconnected-(BOTTOM_HEADER-Pad14)") (class "Default")
      (node (ref "BOTTOM_HEADER") (pin "14") (pinfunction "14_14") (pintype "input+no_connect"))
    )
    (net (code "139") (name "unconnected-(BOTTOM_HEADER-Pad15)") (class "Default")
      (node (ref "BOTTOM_HEADER") (pin "15") (pinfunction "15_15") (pintype "input+no_connect"))
    )
    (net (code "140") (name "unconnected-(BOTTOM_HEADER-Pad19)") (class "Default")
      (node (ref "BOTTOM_HEADER") (pin "19") (pinfunction "19_19") (pintype "input+no_connect"))
    )
    (net (code "141") (name "unconnected-(BOTTOM_HEADER-Pad28)") (class "Default")
      (node (ref "BOTTOM_HEADER") (pin "28") (pinfunction "28_28") (pintype "input+no_connect"))
    )
    (net (code "142") (name "unconnected-(BOTTOM_HEADER-Pad35)") (class "Default")
      (node (ref "BOTTOM_HEADER") (pin "35") (pinfunction "35_35") (pintype "input+no_connect"))
    )
    (net (code "143") (name "unconnected-(BOTTOM_HEADER-Pad36)") (class "Default")
      (node (ref "BOTTOM_HEADER") (pin "36") (pinfunction "36_36") (pintype "input+no_connect"))
    )
    (net (code "144") (name "unconnected-(BOTTOM_HEADER-Pad37)") (class "Default")
      (node (ref "BOTTOM_HEADER") (pin "37") (pinfunction "37_37") (pintype "input+no_connect"))
    )
    (net (code "145") (name "unconnected-(HDMI-SHD-Pad20)") (class "Default")
      (node (ref "HDMI") (pin "20") (pinfunction "SHD_20") (pintype "unspecified"))
    )
    (net (code "146") (name "unconnected-(HDMI-SHD-Pad21)") (class "Default")
      (node (ref "HDMI") (pin "21") (pinfunction "SHD_21") (pintype "unspecified"))
    )
    (net (code "147") (name "unconnected-(HDMI-SHD-Pad22)") (class "Default")
      (node (ref "HDMI") (pin "22") (pinfunction "SHD_22") (pintype "unspecified"))
    )
    (net (code "148") (name "unconnected-(HDMI-SHD-Pad23)") (class "Default")
      (node (ref "HDMI") (pin "23") (pinfunction "SHD_23") (pintype "unspecified"))
    )
    (net (code "149") (name "unconnected-(IC1-!SSPND-Pad28)") (class "Default")
      (node (ref "IC1") (pin "28") (pinfunction "!SSPND_28") (pintype "bidirectional+no_connect"))
    )
    (net (code "150") (name "unconnected-(IC1-DIN-Pad24)") (class "Default")
      (node (ref "IC1") (pin "24") (pinfunction "DIN_24") (pintype "bidirectional+no_connect"))
    )
    (net (code "151") (name "unconnected-(IC1-DOUT-Pad25)") (class "Default")
      (node (ref "IC1") (pin "25") (pinfunction "DOUT_25") (pintype "bidirectional+no_connect"))
    )
    (net (code "152") (name "unconnected-(IC1-HID0-Pad5)") (class "Default")
      (node (ref "IC1") (pin "5") (pinfunction "HID0_5") (pintype "bidirectional"))
    )
    (net (code "153") (name "unconnected-(IC1-HID1-Pad6)") (class "Default")
      (node (ref "IC1") (pin "6") (pinfunction "HID1_6") (pintype "bidirectional"))
    )
    (net (code "154") (name "unconnected-(IC1-HID2-Pad7)") (class "Default")
      (node (ref "IC1") (pin "7") (pinfunction "HID2_7") (pintype "bidirectional"))
    )
    (net (code "155") (name "unconnected-(IC1-SEL0-Pad8)") (class "Default")
      (node (ref "IC1") (pin "8") (pinfunction "SEL0_8") (pintype "bidirectional"))
    )
    (net (code "156") (name "unconnected-(IC1-SEL1-Pad9)") (class "Default")
      (node (ref "IC1") (pin "9") (pinfunction "SEL1_9") (pintype "bidirectional"))
    )
    (net (code "157") (name "unconnected-(IS37SML01G1-NC-Pad3)") (class "Default")
      (node (ref "IS37SML01G1") (pin "3") (pinfunction "NC_3") (pintype "unspecified+no_connect"))
    )
    (net (code "158") (name "unconnected-(IS37SML01G1-NC-Pad4)") (class "Default")
      (node (ref "IS37SML01G1") (pin "4") (pinfunction "NC_4") (pintype "unspecified+no_connect"))
    )
    (net (code "159") (name "unconnected-(IS37SML01G1-NC-Pad5)") (class "Default")
      (node (ref "IS37SML01G1") (pin "5") (pinfunction "NC_5") (pintype "unspecified+no_connect"))
    )
    (net (code "160") (name "unconnected-(IS37SML01G1-NC-Pad6)") (class "Default")
      (node (ref "IS37SML01G1") (pin "6") (pinfunction "NC_6") (pintype "unspecified+no_connect"))
    )
    (net (code "161") (name "unconnected-(IS37SML01G1-NC-Pad11)") (class "Default")
      (node (ref "IS37SML01G1") (pin "11") (pinfunction "NC_11") (pintype "unspecified+no_connect"))
    )
    (net (code "162") (name "unconnected-(IS37SML01G1-NC-Pad12)") (class "Default")
      (node (ref "IS37SML01G1") (pin "12") (pinfunction "NC_12") (pintype "unspecified+no_connect"))
    )
    (net (code "163") (name "unconnected-(IS37SML01G1-NC-Pad13)") (class "Default")
      (node (ref "IS37SML01G1") (pin "13") (pinfunction "NC_13") (pintype "unspecified+no_connect"))
    )
    (net (code "164") (name "unconnected-(IS37SML01G1-NC-Pad14)") (class "Default")
      (node (ref "IS37SML01G1") (pin "14") (pinfunction "NC_14") (pintype "unspecified+no_connect"))
    )
    (net (code "165") (name "unconnected-(TOP_HEADER-Pad13)") (class "Default")
      (node (ref "TOP_HEADER") (pin "13") (pinfunction "13_13") (pintype "input+no_connect"))
    )
    (net (code "166") (name "unconnected-(TOP_HEADER-Pad14)") (class "Default")
      (node (ref "TOP_HEADER") (pin "14") (pinfunction "14_14") (pintype "input+no_connect"))
    )
    (net (code "167") (name "unconnected-(TOP_HEADER-Pad15)") (class "Default")
      (node (ref "TOP_HEADER") (pin "15") (pinfunction "15_15") (pintype "input+no_connect"))
    )
    (net (code "168") (name "unconnected-(TOP_HEADER-Pad16)") (class "Default")
      (node (ref "TOP_HEADER") (pin "16") (pinfunction "16_16") (pintype "input+no_connect"))
    )
    (net (code "169") (name "unconnected-(TOP_HEADER-Pad17)") (class "Default")
      (node (ref "TOP_HEADER") (pin "17") (pinfunction "17_17") (pintype "input+no_connect"))
    )
    (net (code "170") (name "unconnected-(TOP_HEADER-Pad18)") (class "Default")
      (node (ref "TOP_HEADER") (pin "18") (pinfunction "18_18") (pintype "input+no_connect"))
    )
    (net (code "171") (name "unconnected-(TOP_HEADER-Pad19)") (class "Default")
      (node (ref "TOP_HEADER") (pin "19") (pinfunction "19_19") (pintype "input+no_connect"))
    )
    (net (code "172") (name "unconnected-(TOP_HEADER-Pad20)") (class "Default")
      (node (ref "TOP_HEADER") (pin "20") (pinfunction "20_20") (pintype "input+no_connect"))
    )
    (net (code "173") (name "unconnected-(TOP_HEADER-Pad21)") (class "Default")
      (node (ref "TOP_HEADER") (pin "21") (pinfunction "21_21") (pintype "input+no_connect"))
    )
    (net (code "174") (name "unconnected-(TOP_HEADER-Pad22)") (class "Default")
      (node (ref "TOP_HEADER") (pin "22") (pinfunction "22_22") (pintype "input+no_connect"))
    )
    (net (code "175") (name "unconnected-(TOP_HEADER-Pad25)") (class "Default")
      (node (ref "TOP_HEADER") (pin "25") (pinfunction "25_25") (pintype "input+no_connect"))
    )
    (net (code "176") (name "unconnected-(TOP_HEADER-Pad26)") (class "Default")
      (node (ref "TOP_HEADER") (pin "26") (pinfunction "26_26") (pintype "input+no_connect"))
    )
    (net (code "177") (name "unconnected-(TOP_HEADER-Pad29)") (class "Default")
      (node (ref "TOP_HEADER") (pin "29") (pinfunction "29_29") (pintype "input+no_connect"))
    )
    (net (code "178") (name "unconnected-(TOP_HEADER-Pad31)") (class "Default")
      (node (ref "TOP_HEADER") (pin "31") (pinfunction "31_31") (pintype "input+no_connect"))
    )
    (net (code "179") (name "unconnected-(TOP_HEADER-Pad32)") (class "Default")
      (node (ref "TOP_HEADER") (pin "32") (pinfunction "32_32") (pintype "input+no_connect"))
    )
    (net (code "180") (name "unconnected-(TOP_HEADER-Pad35)") (class "Default")
      (node (ref "TOP_HEADER") (pin "35") (pinfunction "35_35") (pintype "input+no_connect"))
    )
    (net (code "181") (name "unconnected-(TOP_HEADER-Pad36)") (class "Default")
      (node (ref "TOP_HEADER") (pin "36") (pinfunction "36_36") (pintype "input+no_connect"))
    )
    (net (code "182") (name "unconnected-(U1-CLK-Pad20)") (class "Default")
      (node (ref "U1") (pin "20") (pinfunction "CLK_20") (pintype "unspecified+no_connect"))
    )
    (net (code "183") (name "unconnected-(U1-CMD-Pad19)") (class "Default")
      (node (ref "U1") (pin "19") (pinfunction "CMD_19") (pintype "unspecified+no_connect"))
    )
    (net (code "184") (name "unconnected-(U1-IO2-Pad24)") (class "Default")
      (node (ref "U1") (pin "24") (pinfunction "IO2_24") (pintype "unspecified+no_connect"))
    )
    (net (code "185") (name "unconnected-(U1-IO4-Pad26)") (class "Default")
      (node (ref "U1") (pin "26") (pinfunction "IO4_26") (pintype "unspecified+no_connect"))
    )
    (net (code "186") (name "unconnected-(U1-IO5-Pad29)") (class "Default")
      (node (ref "U1") (pin "29") (pinfunction "IO5_29") (pintype "unspecified+no_connect"))
    )
    (net (code "187") (name "unconnected-(U1-IO12-Pad14)") (class "Default")
      (node (ref "U1") (pin "14") (pinfunction "IO12_14") (pintype "unspecified+no_connect"))
    )
    (net (code "188") (name "unconnected-(U1-IO14-Pad13)") (class "Default")
      (node (ref "U1") (pin "13") (pinfunction "IO14_13") (pintype "unspecified+no_connect"))
    )
    (net (code "189") (name "unconnected-(U1-IO25-Pad10)") (class "Default")
      (node (ref "U1") (pin "10") (pinfunction "IO25_10") (pintype "unspecified+no_connect"))
    )
    (net (code "190") (name "unconnected-(U1-IO34-Pad6)") (class "Default")
      (node (ref "U1") (pin "6") (pinfunction "IO34_6") (pintype "unspecified+no_connect"))
    )
    (net (code "191") (name "unconnected-(U1-IO35-Pad7)") (class "Default")
      (node (ref "U1") (pin "7") (pinfunction "IO35_7") (pintype "unspecified+no_connect"))
    )
    (net (code "192") (name "unconnected-(U1-NC-Pad32)") (class "Default")
      (node (ref "U1") (pin "32") (pinfunction "NC_32") (pintype "unspecified+no_connect"))
    )
    (net (code "193") (name "unconnected-(U1-SD0-Pad21)") (class "Default")
      (node (ref "U1") (pin "21") (pinfunction "SD0_21") (pintype "unspecified+no_connect"))
    )
    (net (code "194") (name "unconnected-(U1-SD1-Pad22)") (class "Default")
      (node (ref "U1") (pin "22") (pinfunction "SD1_22") (pintype "unspecified+no_connect"))
    )
    (net (code "195") (name "unconnected-(U1-SD2-Pad17)") (class "Default")
      (node (ref "U1") (pin "17") (pinfunction "SD2_17") (pintype "unspecified+no_connect"))
    )
    (net (code "196") (name "unconnected-(U1-SD3-Pad18)") (class "Default")
      (node (ref "U1") (pin "18") (pinfunction "SD3_18") (pintype "unspecified+no_connect"))
    )
    (net (code "197") (name "unconnected-(U1-SENSOR_VN-Pad5)") (class "Default")
      (node (ref "U1") (pin "5") (pinfunction "SENSOR_VN_5") (pintype "unspecified+no_connect"))
    )
    (net (code "198") (name "unconnected-(U1-SENSOR_VP-Pad4)") (class "Default")
      (node (ref "U1") (pin "4") (pinfunction "SENSOR_VP_4") (pintype "unspecified+no_connect"))
    )
    (net (code "199") (name "unconnected-(U2-PB5_(RESET)-Pad1)") (class "Default")
      (node (ref "U2") (pin "1") (pinfunction "PB5_(RESET)_1") (pintype "bidirectional"))
    )
    (net (code "200") (name "unconnected-(U3-3V3-Pad1)") (class "Default")
      (node (ref "U3") (pin "1") (pinfunction "3V3_1") (pintype "unspecified+no_connect"))
    )
    (net (code "201") (name "unconnected-(U3-3V3-Pad2)") (class "Default")
      (node (ref "U3") (pin "2") (pinfunction "3V3_2") (pintype "output+no_connect"))
    )
    (net (code "202") (name "unconnected-(U3-5V-Pad79)") (class "Default")
      (node (ref "U3") (pin "79") (pinfunction "5V_79") (pintype "unspecified+no_connect"))
    )
    (net (code "203") (name "unconnected-(U3-5V-Pad80)") (class "Default")
      (node (ref "U3") (pin "80") (pinfunction "5V_80") (pintype "unspecified+no_connect"))
    )
    (net (code "204") (name "unconnected-(U3-AGND-Pad32)") (class "Default")
      (node (ref "U3") (pin "32") (pinfunction "AGND_32") (pintype "passive+no_connect"))
    )
    (net (code "205") (name "unconnected-(U3-EXP_PRESENT-Pad78)") (class "Default")
      (node (ref "U3") (pin "78") (pinfunction "EXP_PRESENT_78") (pintype "input+no_connect"))
    )
    (net (code "206") (name "unconnected-(U3-GND-Pad10)") (class "Default")
      (node (ref "U3") (pin "10") (pinfunction "GND_10") (pintype "passive+no_connect"))
    )
    (net (code "207") (name "unconnected-(U3-GND-Pad21)") (class "Default")
      (node (ref "U3") (pin "21") (pinfunction "GND_21") (pintype "passive+no_connect"))
    )
    (net (code "208") (name "unconnected-(U3-GND-Pad22)") (class "Default")
      (node (ref "U3") (pin "22") (pinfunction "GND_22") (pintype "passive+no_connect"))
    )
    (net (code "209") (name "unconnected-(U3-GND-Pad33)") (class "Default")
      (node (ref "U3") (pin "33") (pinfunction "GND_33") (pintype "passive+no_connect"))
    )
    (net (code "210") (name "unconnected-(U3-GND-Pad44)") (class "Default")
      (node (ref "U3") (pin "44") (pinfunction "GND_44") (pintype "passive+no_connect"))
    )
    (net (code "211") (name "unconnected-(U3-GND-Pad53)") (class "Default")
      (node (ref "U3") (pin "53") (pinfunction "GND_53") (pintype "passive+no_connect"))
    )
    (net (code "212") (name "unconnected-(U3-GND-Pad54)") (class "Default")
      (node (ref "U3") (pin "54") (pinfunction "GND_54") (pintype "passive+no_connect"))
    )
    (net (code "213") (name "unconnected-(U3-GND-Pad76)") (class "Default")
      (node (ref "U3") (pin "76") (pinfunction "GND_76") (pintype "passive+no_connect"))
    )
    (net (code "214") (name "unconnected-(U3-NC-Pad68)") (class "Default")
      (node (ref "U3") (pin "68") (pinfunction "NC_68") (pintype "unspecified+no_connect"))
    )
    (net (code "215") (name "unconnected-(U3-NC-Pad69)") (class "Default")
      (node (ref "U3") (pin "69") (pinfunction "NC_69") (pintype "unspecified+no_connect"))
    )
    (net (code "216") (name "unconnected-(U3-NC-Pad70)") (class "Default")
      (node (ref "U3") (pin "70") (pinfunction "NC_70") (pintype "unspecified+no_connect"))
    )
    (net (code "217") (name "unconnected-(U3-NC-Pad71)") (class "Default")
      (node (ref "U3") (pin "71") (pinfunction "NC_71") (pintype "unspecified+no_connect"))
    )
    (net (code "218") (name "unconnected-(U3-NC-Pad72)") (class "Default")
      (node (ref "U3") (pin "72") (pinfunction "NC_72") (pintype "unspecified+no_connect"))
    )
    (net (code "219") (name "unconnected-(U3-NC-Pad73)") (class "Default")
      (node (ref "U3") (pin "73") (pinfunction "NC_73") (pintype "unspecified+no_connect"))
    )
    (net (code "220") (name "unconnected-(U3-NC-Pad74)") (class "Default")
      (node (ref "U3") (pin "74") (pinfunction "NC_74") (pintype "unspecified+no_connect"))
    )
    (net (code "221") (name "unconnected-(U3-NC-Pad75)") (class "Default")
      (node (ref "U3") (pin "75") (pinfunction "NC_75") (pintype "unspecified+no_connect"))
    )
    (net (code "222") (name "unconnected-(U3-NC-Pad77)") (class "Default")
      (node (ref "U3") (pin "77") (pinfunction "NC_77") (pintype "unspecified+no_connect"))
    )
    (net (code "223") (name "unconnected-(U3-P1-I-CLK12-DIFFCLK_7n-B4-T9-Pad5)") (class "Default")
      (node (ref "U3") (pin "5") (pinfunction "P1-I-CLK12-DIFFCLK_7n-B4-T9_5") (pintype "bidirectional+no_connect"))
    )
    (net (code "224") (name "unconnected-(U3-P2-I-CLK13-DIFFCLK_7p-B4-R9-Pad7)") (class "Default")
      (node (ref "U3") (pin "7") (pinfunction "P2-I-CLK13-DIFFCLK_7p-B4-R9_7") (pintype "bidirectional+no_connect"))
    )
    (net (code "225") (name "unconnected-(U3-P3-IO-DIFFIO_B2p-DQ3B-DQ5B-B3-R3-Pad9)") (class "Default")
      (node (ref "U3") (pin "9") (pinfunction "P3-IO-DIFFIO_B2p-DQ3B-DQ5B-B3-R3_9") (pintype "bidirectional+no_connect"))
    )
    (net (code "226") (name "unconnected-(U3-P4-IO-DIFFIO_B12n-DQ5B-B3-P8-Pad11)") (class "Default")
      (node (ref "U3") (pin "11") (pinfunction "P4-IO-DIFFIO_B12n-DQ5B-B3-P8_11") (pintype "bidirectional+no_connect"))
    )
    (net (code "227") (name "unconnected-(U3-P5-IO-DIFFIO_L15n-DM1L-nBWS1L-B2-P1-Pad13)") (class "Default")
      (node (ref "U3") (pin "13") (pinfunction "P5-IO-DIFFIO_L15n-DM1L-nBWS1L-B2-P1_13") (pintype "bidirectional+no_connect"))
    )
    (net (code "228") (name "unconnected-(U3-P6-IO-DIFFIO_B10n-DM5B-nBWS5B-DM5B0-nBWS5B1-B3-M8-Pad15)") (class "Default")
      (node (ref "U3") (pin "15") (pinfunction "P6-IO-DIFFIO_B10n-DM5B-nBWS5B-DM5B0-nBWS5B1-B3-M8_15") (pintype "bidirectional+no_connect"))
    )
    (net (code "229") (name "unconnected-(U3-P7-IO-DIFFIO_L15p-DQ1L-B2-P2-Pad17)") (class "Default")
      (node (ref "U3") (pin "17") (pinfunction "P7-IO-DIFFIO_L15p-DQ1L-B2-P2_17") (pintype "bidirectional+no_connect"))
    )
    (net (code "230") (name "unconnected-(U3-P8-IO-DIFFIO_B4n-DQ3B-DQ5B-B3-N6-Pad19)") (class "Default")
      (node (ref "U3") (pin "19") (pinfunction "P8-IO-DIFFIO_B4n-DQ3B-DQ5B-B3-N6_19") (pintype "bidirectional+no_connect"))
    )
    (net (code "231") (name "unconnected-(U3-P9-IO-DQS3L-nCQ3L-CDPCLK1-B2-R1-Pad23)") (class "Default")
      (node (ref "U3") (pin "23") (pinfunction "P9-IO-DQS3L-nCQ3L-CDPCLK1-B2-R1_23") (pintype "bidirectional+no_connect"))
    )
    (net (code "232") (name "unconnected-(U3-P10-IO-DIFFIO_B4p-DQ3B-DQ5B-B3-N5-Pad25)") (class "Default")
      (node (ref "U3") (pin "25") (pinfunction "P10-IO-DIFFIO_B4p-DQ3B-DQ5B-B3-N5_25") (pintype "bidirectional+no_connect"))
    )
    (net (code "233") (name "unconnected-(U3-P11-IO-DIFFIO_L10n-DQ1L-B2-K1-Pad27)") (class "Default")
      (node (ref "U3") (pin "27") (pinfunction "P11-IO-DIFFIO_L10n-DQ1L-B2-K1_27") (pintype "bidirectional+no_connect"))
    )
    (net (code "234") (name "unconnected-(U3-P12-IO-DIFFIO_L10p-B2-K2-Pad29)") (class "Default")
      (node (ref "U3") (pin "29") (pinfunction "P12-IO-DIFFIO_L10p-B2-K2_29") (pintype "bidirectional+no_connect"))
    )
    (net (code "235") (name "unconnected-(U3-P13-IO-VREFB4N0-B4-P11-Pad31)") (class "Default")
      (node (ref "U3") (pin "31") (pinfunction "P13-IO-VREFB4N0-B4-P11_31") (pintype "bidirectional+no_connect"))
    )
    (net (code "236") (name "unconnected-(U3-P14-IO-DIFFIO_L11p-DQS1L-nCQ1L-DPCLK1-B2-L2-Pad35)") (class "Default")
      (node (ref "U3") (pin "35") (pinfunction "P14-IO-DIFFIO_L11p-DQS1L-nCQ1L-DPCLK1-B2-L2_35") (pintype "bidirectional+no_connect"))
    )
    (net (code "237") (name "unconnected-(U3-P15-IO-DIFFIO_R15n-DQS3R-nCQ3R-CDPCLK4-B5-P16-Pad37)") (class "Default")
      (node (ref "U3") (pin "37") (pinfunction "P15-IO-DIFFIO_R15n-DQS3R-nCQ3R-CDPCLK4-B5-P16_37") (pintype "bidirectional+no_connect"))
    )
    (net (code "238") (name "unconnected-(U3-P16-IO-DIFFIO_B1n-DM3B-nBWS3B-DM5B1-nBWS5B2-B3-P3-Pad39)") (class "Default")
      (node (ref "U3") (pin "39") (pinfunction "P16-IO-DIFFIO_B1n-DM3B-nBWS3B-DM5B1-nBWS5B2-B3-P3_39") (pintype "bidirectional+no_connect"))
    )
    (net (code "239") (name "unconnected-(U3-P17-IO-DIFFIO_L13n-DQ1L-B2-N1-Pad41)") (class "Default")
      (node (ref "U3") (pin "41") (pinfunction "P17-IO-DIFFIO_L13n-DQ1L-B2-N1_41") (pintype "bidirectional+no_connect"))
    )
    (net (code "240") (name "unconnected-(U3-P18-IO-RDN1-DQ1L-B2-L4-Pad43)") (class "Default")
      (node (ref "U3") (pin "43") (pinfunction "P18-IO-RDN1-DQ1L-B2-L4_43") (pintype "bidirectional+no_connect"))
    )
    (net (code "241") (name "unconnected-(U3-P19-IO-VREFB2N0-B2-L3-Pad45)") (class "Default")
      (node (ref "U3") (pin "45") (pinfunction "P19-IO-VREFB2N0-B2-L3_45") (pintype "bidirectional+no_connect"))
    )
    (net (code "242") (name "unconnected-(U3-P20-IO-DIFFIO_L7n-DQ1L-B2-J1-Pad47)") (class "Default")
      (node (ref "U3") (pin "47") (pinfunction "P20-IO-DIFFIO_L7n-DQ1L-B2-J1_47") (pintype "bidirectional+no_connect"))
    )
    (net (code "243") (name "unconnected-(U3-P21-IO-DIFFIO_B16n-DQS4B-CQ5B-DPCLK4-B4-T10-Pad49)") (class "Default")
      (node (ref "U3") (pin "49") (pinfunction "P21-IO-DIFFIO_B16n-DQS4B-CQ5B-DPCLK4-B4-T10_49") (pintype "bidirectional+no_connect"))
    )
    (net (code "244") (name "unconnected-(U3-P22-IO-DIFFIO_L6p-DQS0L-CQ1L-DPCLK0-B1-G2-Pad51)") (class "Default")
      (node (ref "U3") (pin "51") (pinfunction "P22-IO-DIFFIO_L6p-DQS0L-CQ1L-DPCLK0-B1-G2_51") (pintype "bidirectional+no_connect"))
    )
    (net (code "245") (name "unconnected-(U3-P23-IO-DIFFIO_L6n-B1-G1-Pad55)") (class "Default")
      (node (ref "U3") (pin "55") (pinfunction "P23-IO-DIFFIO_L6n-B1-G1_55") (pintype "bidirectional+no_connect"))
    )
    (net (code "246") (name "unconnected-(U3-P24-IO-RUP3-DM1R-nBWS1R-B5-N14-Pad57)") (class "Default")
      (node (ref "U3") (pin "57") (pinfunction "P24-IO-RUP3-DM1R-nBWS1R-B5-N14_57") (pintype "bidirectional+no_connect"))
    )
    (net (code "247") (name "unconnected-(U3-P25-IO-DIFFIO_L5n-B1-F1-Pad59)") (class "Default")
      (node (ref "U3") (pin "59") (pinfunction "P25-IO-DIFFIO_L5n-B1-F1_59") (pintype "bidirectional+no_connect"))
    )
    (net (code "248") (name "unconnected-(U3-P26-IO-DIFFIO_R11n-DQ1R-B5-L16-Pad61)") (class "Default")
      (node (ref "U3") (pin "61") (pinfunction "P26-IO-DIFFIO_R11n-DQ1R-B5-L16_61") (pintype "bidirectional+no_connect"))
    )
    (net (code "249") (name "unconnected-(U3-P27-IO-DIFFIO_L5p-B1-F2-Pad63)") (class "Default")
      (node (ref "U3") (pin "63") (pinfunction "P27-IO-DIFFIO_L5p-B1-F2_63") (pintype "bidirectional+no_connect"))
    )
    (net (code "250") (name "unconnected-(U3-P28-IO-DIFFIO_R7n-DQ1R-B5-J13-Pad65)") (class "Default")
      (node (ref "U3") (pin "65") (pinfunction "P28-IO-DIFFIO_R7n-DQ1R-B5-J13_65") (pintype "bidirectional+no_connect"))
    )
    (net (code "251") (name "unconnected-(U3-P29-IO-RUP2-B4-M10-Pad67)") (class "Default")
      (node (ref "U3") (pin "67") (pinfunction "P29-IO-RUP2-B4-M10_67") (pintype "bidirectional+no_connect"))
    )
    (net (code "252") (name "unconnected-(U3-P35-I-CLK14-DIFFCLK_6n-B3-T8-Pad6)") (class "Default")
      (node (ref "U3") (pin "6") (pinfunction "P35-I-CLK14-DIFFCLK_6n-B3-T8_6") (pintype "bidirectional+no_connect"))
    )
    (net (code "253") (name "unconnected-(U3-P36-I-CLK15-DIFFCLK_6p-B3-R8-Pad8)") (class "Default")
      (node (ref "U3") (pin "8") (pinfunction "P36-I-CLK15-DIFFCLK_6p-B3-R8_8") (pintype "bidirectional+no_connect"))
    )
    (net (code "254") (name "unconnected-(U3-P37-IO-VREFB3N0-B3-P6-Pad12)") (class "Default")
      (node (ref "U3") (pin "12") (pinfunction "P37-IO-VREFB3N0-B3-P6_12") (pintype "bidirectional+no_connect"))
    )
    (net (code "255") (name "unconnected-(U3-P38-IO-DIFFIO_B11p-DQ5B-B3-N8-Pad14)") (class "Default")
      (node (ref "U3") (pin "14") (pinfunction "P38-IO-DIFFIO_B11p-DQ5B-B3-N8_14") (pintype "bidirectional+no_connect"))
    )
    (net (code "256") (name "unconnected-(U3-P39-IO-DIFFIO_B5p-DQS3B-nCQ3B-DPCLK2-B3-M7-Pad16)") (class "Default")
      (node (ref "U3") (pin "16") (pinfunction "P39-IO-DIFFIO_B5p-DQS3B-nCQ3B-DPCLK2-B3-M7_16") (pintype "bidirectional+no_connect"))
    )
    (net (code "257") (name "unconnected-(U3-P40-IO-DIFFIO_B9n-DQ3B-DQ5B-B3-L8-Pad18)") (class "Default")
      (node (ref "U3") (pin "18") (pinfunction "P40-IO-DIFFIO_B9n-DQ3B-DQ5B-B3-L8_18") (pintype "bidirectional+no_connect"))
    )
    (net (code "258") (name "unconnected-(U3-P41-IO-DQ3B-DQ5B-B3-L7-Pad20)") (class "Default")
      (node (ref "U3") (pin "20") (pinfunction "P41-IO-DQ3B-DQ5B-B3-L7_20") (pintype "bidirectional+no_connect"))
    )
    (net (code "259") (name "unconnected-(U3-P42-IO-DQ3B-DQ5B-B3-M6-Pad24)") (class "Default")
      (node (ref "U3") (pin "24") (pinfunction "P42-IO-DQ3B-DQ5B-B3-M6_24") (pintype "bidirectional+no_connect"))
    )
    (net (code "260") (name "unconnected-(U3-P43-IO-DQS1B-nCQ1B-CDPCLK2-B3-T2-Pad26)") (class "Default")
      (node (ref "U3") (pin "26") (pinfunction "P43-IO-DQS1B-nCQ1B-CDPCLK2-B3-T2_26") (pintype "bidirectional+no_connect"))
    )
    (net (code "261") (name "unconnected-(U3-P44-IO-B1-G5-Pad28)") (class "Default")
      (node (ref "U3") (pin "28") (pinfunction "P44-IO-B1-G5_28") (pintype "bidirectional+no_connect"))
    )
    (net (code "262") (name "unconnected-(U3-P45-IO-VREFB1N0-B1-F3-Pad30)") (class "Default")
      (node (ref "U3") (pin "30") (pinfunction "P45-IO-VREFB1N0-B1-F3_30") (pintype "bidirectional+no_connect"))
    )
    (net (code "263") (name "unconnected-(U3-P46-IO-DIFFIO_R13n-DQ1R-B5-N16-Pad34)") (class "Default")
      (node (ref "U3") (pin "34") (pinfunction "P46-IO-DIFFIO_R13n-DQ1R-B5-N16_34") (pintype "bidirectional+no_connect"))
    )
    (net (code "264") (name "unconnected-(U3-P47-IO-DIFFIO_L11n-B2-L1-Pad36)") (class "Default")
      (node (ref "U3") (pin "36") (pinfunction "P47-IO-DIFFIO_L11n-B2-L1_36") (pintype "bidirectional+no_connect"))
    )
    (net (code "265") (name "unconnected-(U3-P48-IO-DIFFIO_R15p-DQ1R-B5-R16-Pad38)") (class "Default")
      (node (ref "U3") (pin "38") (pinfunction "P48-IO-DIFFIO_R15p-DQ1R-B5-R16_38") (pintype "bidirectional+no_connect"))
    )
    (net (code "266") (name "unconnected-(U3-P49-IO-DIFFIO_B1p-B3-N3-Pad40)") (class "Default")
      (node (ref "U3") (pin "40") (pinfunction "P49-IO-DIFFIO_B1p-B3-N3_40") (pintype "bidirectional+no_connect"))
    )
    (net (code "267") (name "unconnected-(U3-P50-IO-DIFFIO_L13p-DQ1L-B2-N2-Pad42)") (class "Default")
      (node (ref "U3") (pin "42") (pinfunction "P50-IO-DIFFIO_L13p-DQ1L-B2-N2_42") (pintype "bidirectional+no_connect"))
    )
    (net (code "268") (name "unconnected-(U3-P51-IO-DIFFIO_L7p-DQ1L-B2-J2-Pad46)") (class "Default")
      (node (ref "U3") (pin "46") (pinfunction "P51-IO-DIFFIO_L7p-DQ1L-B2-J2_46") (pintype "bidirectional+no_connect"))
    )
    (net (code "269") (name "unconnected-(U3-P52-IO-DIFFIO_B17n-B4-T11-Pad48)") (class "Default")
      (node (ref "U3") (pin "48") (pinfunction "P52-IO-DIFFIO_B17n-B4-T11_48") (pintype "bidirectional+no_connect"))
    )
    (net (code "270") (name "unconnected-(U3-P53-IO-RDN2-B4-N11-Pad50)") (class "Default")
      (node (ref "U3") (pin "50") (pinfunction "P53-IO-RDN2-B4-N11_50") (pintype "bidirectional+no_connect"))
    )
    (net (code "271") (name "unconnected-(U3-P54-IO-PLL4_CLKOUTp-B4-P14-Pad52)") (class "Default")
      (node (ref "U3") (pin "52") (pinfunction "P54-IO-PLL4_CLKOUTp-B4-P14_52") (pintype "bidirectional+no_connect"))
    )
    (net (code "272") (name "unconnected-(U3-P55-IO-DIFFIO_B24p-B4-N12-Pad56)") (class "Default")
      (node (ref "U3") (pin "56") (pinfunction "P55-IO-DIFFIO_B24p-B4-N12_56") (pintype "bidirectional+no_connect"))
    )
    (net (code "273") (name "unconnected-(U3-P56-IO-VREFB5N0-B5-L14-Pad58)") (class "Default")
      (node (ref "U3") (pin "58") (pinfunction "P56-IO-VREFB5N0-B5-L14_58") (pintype "bidirectional+no_connect"))
    )
    (net (code "274") (name "unconnected-(U3-P57-IO-DIFFIO_R11p-B5-L15-Pad60)") (class "Default")
      (node (ref "U3") (pin "60") (pinfunction "P57-IO-DIFFIO_R11p-B5-L15_60") (pintype "bidirectional+no_connect"))
    )
    (net (code "275") (name "unconnected-(U3-P58-IO-DIFFIO_R10p-DQS1R-nCQ1R-DPCLK6-B5-K15-Pad62)") (class "Default")
      (node (ref "U3") (pin "62") (pinfunction "P58-IO-DIFFIO_R10p-DQS1R-nCQ1R-DPCLK6-B5-K15_62") (pintype "bidirectional+no_connect"))
    )
    (net (code "276") (name "unconnected-(U3-P59-IO-DIFFIO_R8n-DQ1R-B5-J14-Pad64)") (class "Default")
      (node (ref "U3") (pin "64") (pinfunction "P59-IO-DIFFIO_R8n-DQ1R-B5-J14_64") (pintype "bidirectional+no_connect"))
    )
    (net (code "277") (name "unconnected-(U3-P60-IO-DIFFIO_B8n-DQS5B-nCQ5B-DPCLK3-B3-T7-Pad66)") (class "Default")
      (node (ref "U3") (pin "66") (pinfunction "P60-IO-DIFFIO_B8n-DQS5B-nCQ5B-DPCLK3-B3-T7_66") (pintype "bidirectional+no_connect"))
    )
    (net (code "278") (name "unconnected-(U3-nPWREN2-Pad4)") (class "Default")
      (node (ref "U3") (pin "4") (pinfunction "nPWREN2_4") (pintype "input+no_connect"))
    )
    (net (code "279") (name "unconnected-(U3-nRESET_EXP-Pad3)") (class "Default")
      (node (ref "U3") (pin "3") (pinfunction "nRESET_EXP_3") (pintype "input+no_connect"))
    )
    (net (code "280") (name "unconnected-(U4-DM4-Pad23)") (class "Default")
      (node (ref "U4") (pin "23") (pinfunction "DM4_23") (pintype "bidirectional+no_connect"))
    )
    (net (code "281") (name "unconnected-(U4-DP4-Pad24)") (class "Default")
      (node (ref "U4") (pin "24") (pinfunction "DP4_24") (pintype "bidirectional+no_connect"))
    )
    (net (code "282") (name "unconnected-(U4-EECLK-Pad5)") (class "Default")
      (node (ref "U4") (pin "5") (pinfunction "EECLK_5") (pintype "unspecified+no_connect"))
    )
    (net (code "283") (name "unconnected-(U4-PWRON1-Pad9)") (class "Default")
      (node (ref "U4") (pin "9") (pinfunction "PWRON1_9") (pintype "output+no_connect"))
    )
    (net (code "284") (name "unconnected-(U4-PWRON2-Pad13)") (class "Default")
      (node (ref "U4") (pin "13") (pinfunction "PWRON2_13") (pintype "output+no_connect"))
    )
    (net (code "285") (name "unconnected-(U4-PWRON3-Pad17)") (class "Default")
      (node (ref "U4") (pin "17") (pinfunction "PWRON3_17") (pintype "output+no_connect"))
    )
    (net (code "286") (name "unconnected-(U4-PWRON4-Pad21)") (class "Default")
      (node (ref "U4") (pin "21") (pinfunction "PWRON4_21") (pintype "output+no_connect"))
    )
    (net (code "287") (name "unconnected-(U4-SUSPND-Pad32)") (class "Default")
      (node (ref "U4") (pin "32") (pinfunction "SUSPND_32") (pintype "output+no_connect"))
    )
    (net (code "288") (name "unconnected-(U7-CTS#-Pad9)") (class "Default")
      (node (ref "U7") (pin "9") (pinfunction "CTS#_9") (pintype "unspecified+no_connect"))
    )
    (net (code "289") (name "unconnected-(U7-DCD#-Pad12)") (class "Default")
      (node (ref "U7") (pin "12") (pinfunction "DCD#_12") (pintype "unspecified+no_connect"))
    )
    (net (code "290") (name "unconnected-(U7-DSR#-Pad10)") (class "Default")
      (node (ref "U7") (pin "10") (pinfunction "DSR#_10") (pintype "unspecified+no_connect"))
    )
    (net (code "291") (name "unconnected-(U7-R232-Pad15)") (class "Default")
      (node (ref "U7") (pin "15") (pinfunction "R232_15") (pintype "unspecified+no_connect"))
    )
    (net (code "292") (name "unconnected-(U7-RI-Pad11)") (class "Default")
      (node (ref "U7") (pin "11") (pinfunction "RI_11") (pintype "unspecified+no_connect"))
    )
    (net (code "293") (name "unconnected-(U9-CTS#-Pad9)") (class "Default")
      (node (ref "U9") (pin "9") (pinfunction "CTS#_9") (pintype "unspecified+no_connect"))
    )
    (net (code "294") (name "unconnected-(U9-DCD#-Pad12)") (class "Default")
      (node (ref "U9") (pin "12") (pinfunction "DCD#_12") (pintype "unspecified+no_connect"))
    )
    (net (code "295") (name "unconnected-(U9-DSR#-Pad10)") (class "Default")
      (node (ref "U9") (pin "10") (pinfunction "DSR#_10") (pintype "unspecified+no_connect"))
    )
    (net (code "296") (name "unconnected-(U9-DTR#-Pad13)") (class "Default")
      (node (ref "U9") (pin "13") (pinfunction "DTR#_13") (pintype "unspecified+no_connect"))
    )
    (net (code "297") (name "unconnected-(U9-R232-Pad15)") (class "Default")
      (node (ref "U9") (pin "15") (pinfunction "R232_15") (pintype "unspecified+no_connect"))
    )
    (net (code "298") (name "unconnected-(U9-RI-Pad11)") (class "Default")
      (node (ref "U9") (pin "11") (pinfunction "RI_11") (pintype "unspecified+no_connect"))
    )
    (net (code "299") (name "unconnected-(U9-RTS#-Pad14)") (class "Default")
      (node (ref "U9") (pin "14") (pinfunction "RTS#_14") (pintype "unspecified+no_connect"))
    )
    (net (code "300") (name "unconnected-(U12-NC-Pad5)") (class "Default")
      (node (ref "U12") (pin "5") (pinfunction "NC_5") (pintype "unspecified+no_connect"))
    )
    (net (code "301") (name "unconnected-(U12-ZEROA-Pad11)") (class "Default")
      (node (ref "U12") (pin "11") (pinfunction "ZEROA_11") (pintype "unspecified+no_connect"))
    )
    (net (code "302") (name "unconnected-(U13-NC-Pad9)") (class "Default")
      (node (ref "U13") (pin "9") (pinfunction "NC_9") (pintype "unspecified+no_connect"))
    )
    (net (code "303") (name "unconnected-(U13-SHND-Pad12)") (class "Default")
      (node (ref "U13") (pin "12") (pinfunction "SHND_12") (pintype "unspecified+no_connect"))
    )
    (net (code "304") (name "unconnected-(USB_MASTER-Pad0)") (class "Default")
      (node (ref "USB_MASTER") (pin "0") (pinfunction "0_0") (pintype "unspecified+no_connect"))
    )
    (net (code "305") (name "unconnected-(USB_MASTER-Pad0)_1") (class "Default")
      (node (ref "USB_MASTER") (pin "0") (pinfunction "0_0") (pintype "unspecified+no_connect"))
    )
    (net (code "306") (name "unconnected-(USB_MASTER-Pad0)_2") (class "Default")
      (node (ref "USB_MASTER") (pin "0") (pinfunction "0_0") (pintype "unspecified+no_connect"))
    )
    (net (code "307") (name "unconnected-(USB_MASTER-Pad0)_3") (class "Default")
      (node (ref "USB_MASTER") (pin "0") (pinfunction "0_0") (pintype "unspecified+no_connect"))
    )
  )
)
